# M5_CORE2_re.net
KiCad netlist of a schematic drawn in Altium Designer
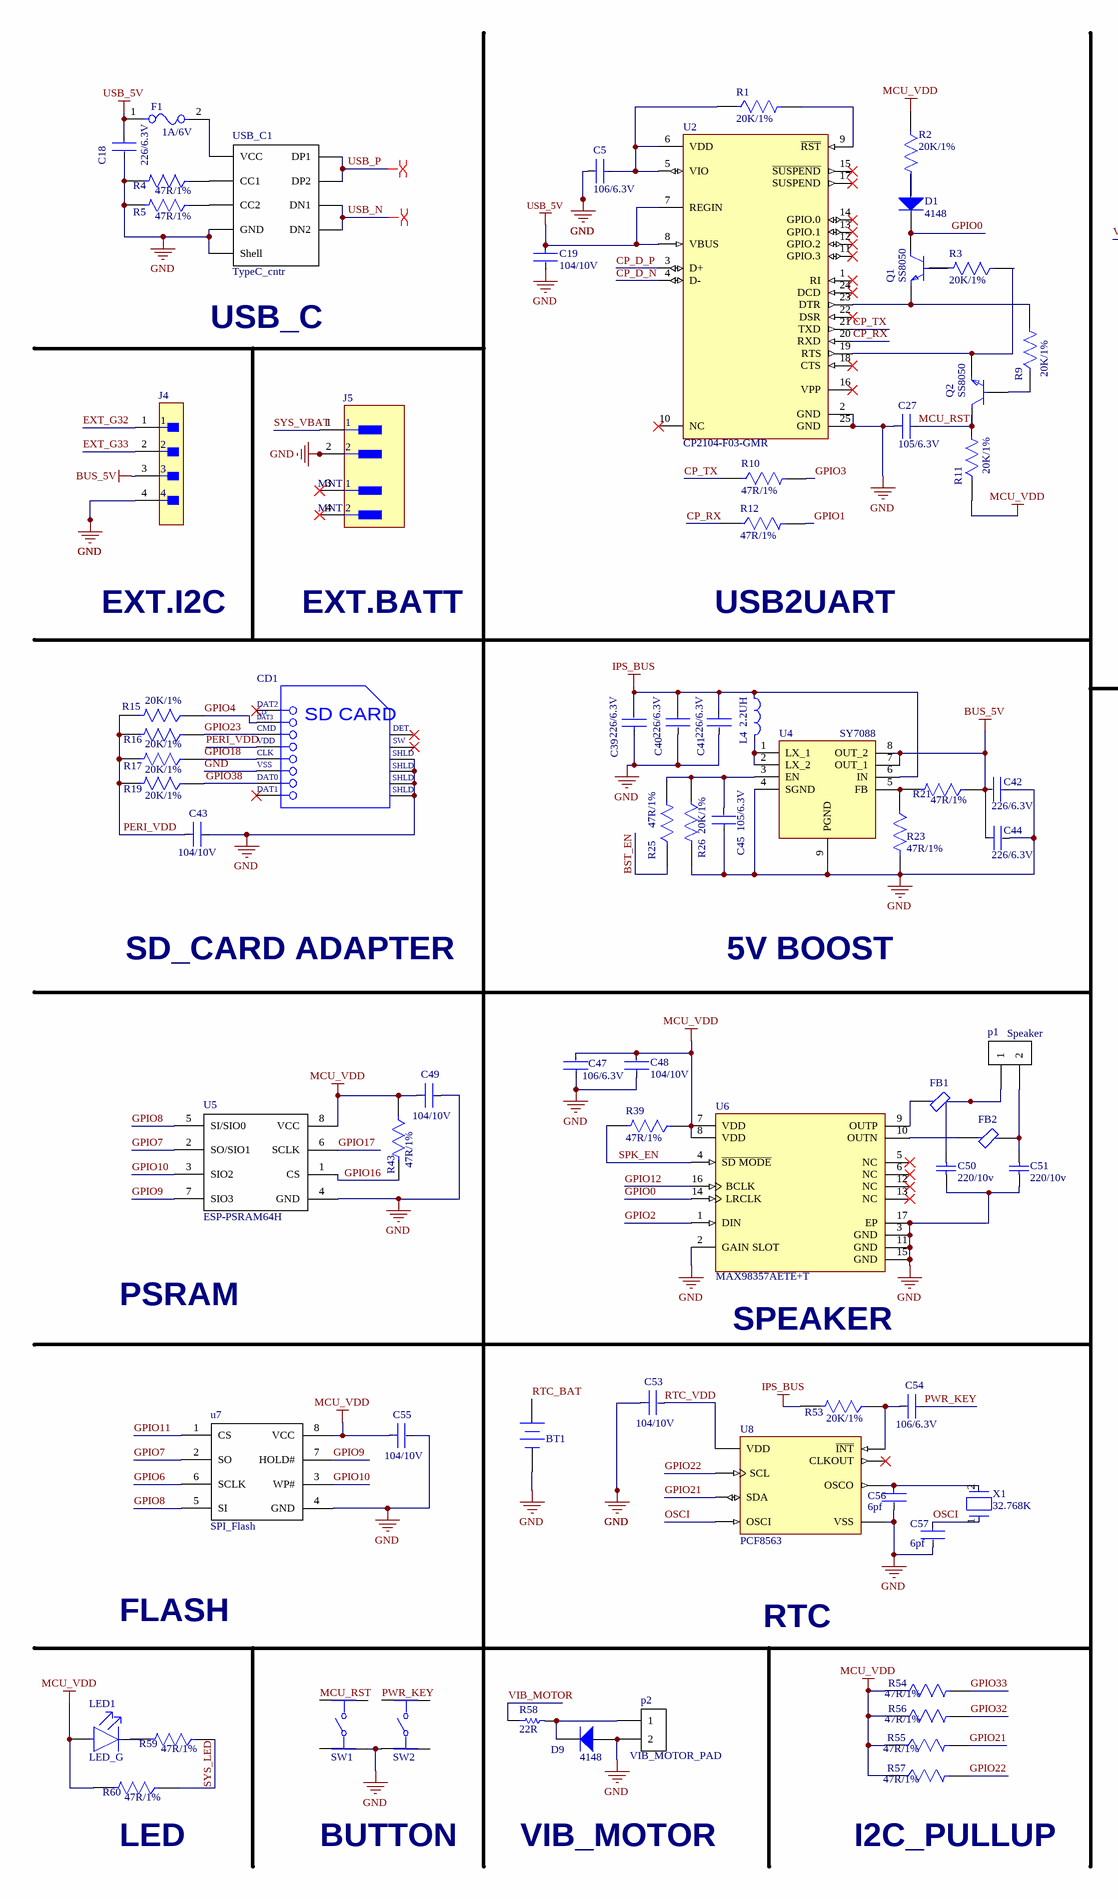
[diagram p0: M5_CORE2_re.SchDoc, left]
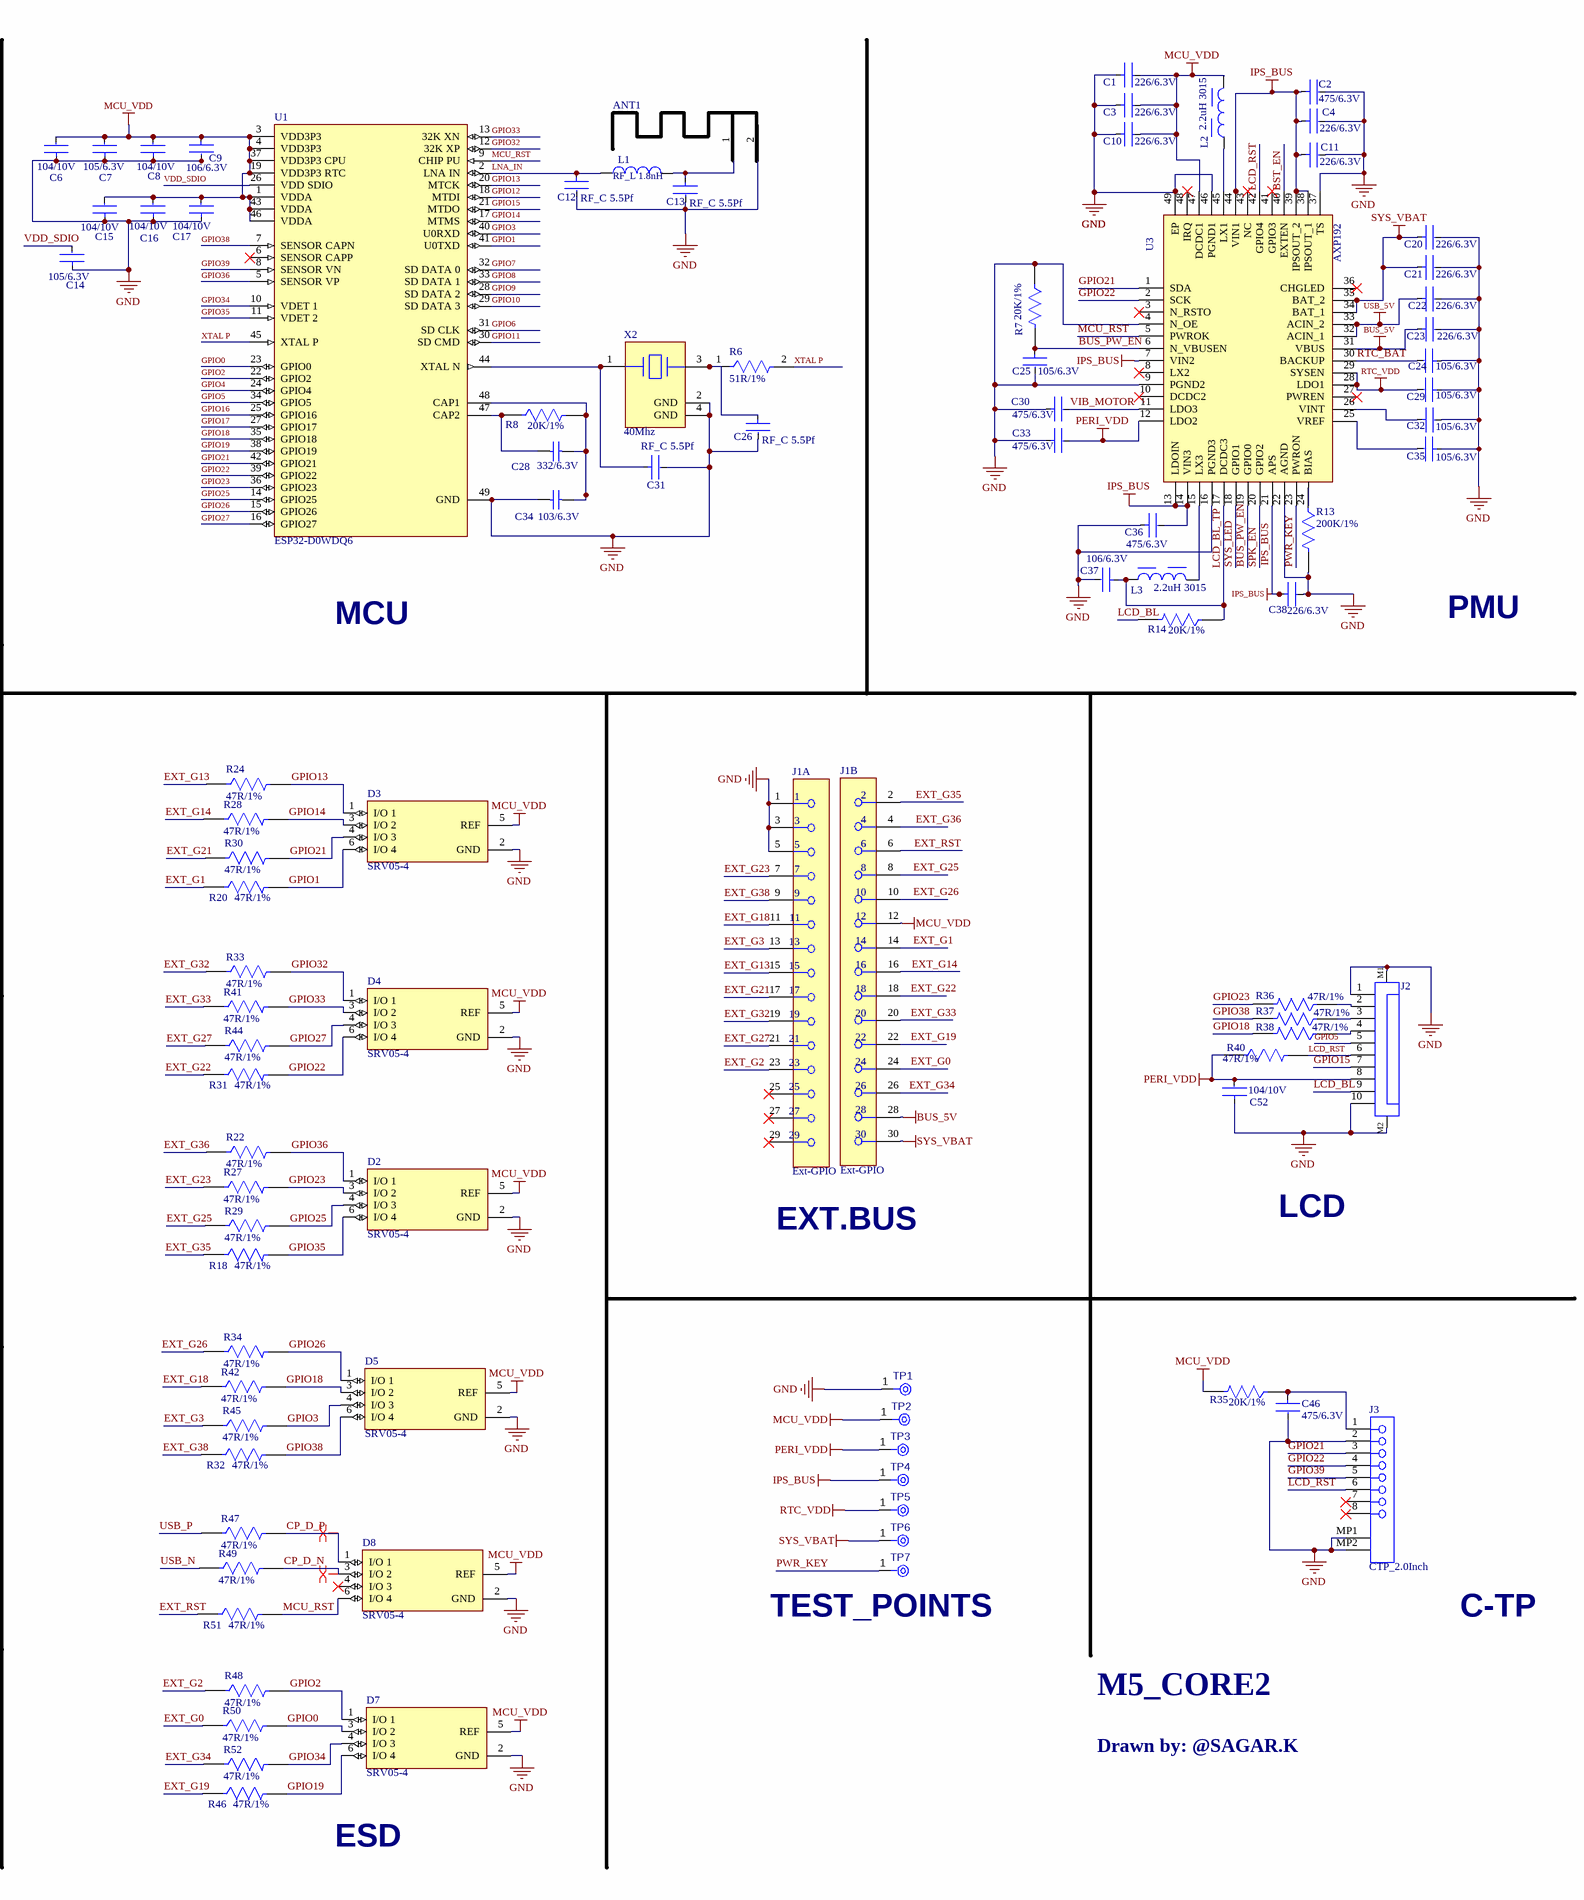
[diagram p1: M5_CORE2_re.SchDoc, right]

(export (version "E")
  (design (tool "Eeschema 10.0.6"))
  (components
    (comp (ref "ANT1")
      (value "2.4GHz_PCB-Antenna")
      (footprint "2.4GHZ_PCB-Antenna")
      (description "Generic symbol for PCB Antenna,")
      (libsource (lib "myLibs") (part "2.4GHz_PCB-Antenna"))
    )
    (comp (ref "BT1")
      (value "MS621FE-FL11E")
      (footprint "SEIK-MS621FE-FL11E-2_V")
      (description "MS Lihium Rechargeable Battery, 3 V, -20 to 60 degC, Tray")
      (fields (field (name "MANUFACTURER") "SeikoInstruments"))
      (libsource (lib "Altium Content Vault") (part "BATTERY_SINGLE-2"))
    )
    (comp (ref "C1")
      (value "226/6.3V")
      (footprint "FP-CL05A226MQ5N6J8-IPC_C")
      (description "CAP CER 22UF 6.3V X5R 0402")
      (fields
        (field (name "MANUFACTURER PART NUMBER") "CL05A226MQ5N6J8")
        (field (name "MANUFACTURER") "Samsung")
      )
      (libsource (lib "myLibs") (part "CMP-13271-000001-1"))
    )
    (comp (ref "C2")
      (value "475/6.3V")
      (footprint "FP-GRM155-0_1-IPC_B")
      (description "Chip Multilayer Ceramic Capacitors for General Purpose, 0402, 4.7uF, X5R, 15%, 20%, 6.3V")
      (fields (field (name "VOLTAGE") "6.3V") (field (name "TOLERANCE") "20%"))
      (libsource (lib "myLibs") (part "CMP-2008-04549-2"))
    )
    (comp (ref "C3")
      (value "226/6.3V")
      (footprint "FP-CL05A226MQ5N6J8-IPC_C")
      (description "CAP CER 22UF 6.3V X5R 0402")
      (fields
        (field (name "MANUFACTURER PART NUMBER") "CL05A226MQ5N6J8")
        (field (name "MANUFACTURER") "Samsung")
      )
      (libsource (lib "myLibs") (part "CMP-13271-000001-1"))
    )
    (comp (ref "C4")
      (value "226/6.3V")
      (footprint "FP-CL05A226MQ5N6J8-IPC_C")
      (description "CAP CER 22UF 6.3V X5R 0402")
      (fields
        (field (name "MANUFACTURER PART NUMBER") "CL05A226MQ5N6J8")
        (field (name "MANUFACTURER") "Samsung")
      )
      (libsource (lib "myLibs") (part "CMP-13271-000001-1"))
    )
    (comp (ref "C5")
      (value "106/6.3V")
      (footprint "FP-GRM155-0_1-IPC_B")
      (description "CAP CER 10UF 6.3V X5R 0603")
      (fields
        (field (name "MANUFACTURER PART NUMBER") "C0603C106M9PACTU")
        (field (name "MANUFACTURER") "KEMET")
      )
      (libsource (lib "myLibs") (part "CMP-2006-02285-3"))
    )
    (comp (ref "C6")
      (value "104/10V")
      (footprint "FP-C0402-BB-MFG")
      (description "CAP CER 0.1UF 10V X5R 0402")
      (fields (field (name "MANUFACTURER") "KEMET") (field (name "TOLERANCE") "0.1"))
      (libsource (lib "myLibs") (part "CMP-2008-02046-2"))
    )
    (comp (ref "C7")
      (value "105/6.3V")
      (footprint "FP-C0402C105K9PACTU-MFG")
      (description "CAP CER 1UF 6.3V X5R 0402")
      (fields (field (name "TOLERANCE") "10%") (field (name "VOLTAGE") "6.3V"))
      (libsource (lib "myLibs") (part "CMP-2008-02075-2"))
    )
    (comp (ref "C8")
      (value "104/10V")
      (footprint "FP-C0402-BB-MFG")
      (description "CAP CER 0.1UF 10V X5R 0402")
      (fields (field (name "MANUFACTURER") "KEMET") (field (name "TOLERANCE") "0.1"))
      (libsource (lib "myLibs") (part "CMP-2008-02046-2"))
    )
    (comp (ref "C9")
      (value "106/6.3V")
      (footprint "FP-GRM155-0_2-IPC_B")
      (description "CAP CER 10UF 6.3V X5R 0402")
      (fields (field (name "VOLTAGE") "6.3V") (field (name "TOLERANCE") "20%"))
      (libsource (lib "myLibs") (part "CMP-2000-05265-2"))
    )
    (comp (ref "C10")
      (value "226/6.3V")
      (footprint "FP-CL05A226MQ5N6J8-IPC_C")
      (description "CAP CER 22UF 6.3V X5R 0402")
      (fields
        (field (name "MANUFACTURER PART NUMBER") "CL05A226MQ5N6J8")
        (field (name "MANUFACTURER") "Samsung")
      )
      (libsource (lib "myLibs") (part "CMP-13271-000001-1"))
    )
    (comp (ref "C11")
      (value "226/6.3V")
      (footprint "FP-CL05A226MQ5N6J8-IPC_C")
      (description "CAP CER 22UF 6.3V X5R 0402")
      (fields
        (field (name "MANUFACTURER PART NUMBER") "CL05A226MQ5N6J8")
        (field (name "MANUFACTURER") "Samsung")
      )
      (libsource (lib "myLibs") (part "CMP-13271-000001-1"))
    )
    (comp (ref "C12")
      (value "RF_C 5.5Pf")
      (footprint "FP-GJM155-0_05-IPC_C")
      (description "Multi-Layer Ceramic Capacitor 5.5pF C0G  ±0.05pF 0402 Paper T/R")
      (fields
        (field (name "MANUFACTURER") "Murata")
        (field (name "MANUFACTURER PART NUMBER") "GJM1555C1H5R5WB01D")
      )
      (libsource (lib "myLibs") (part "CMP-06035-038280-1"))
    )
    (comp (ref "C13")
      (value "RF_C 5.5Pf")
      (footprint "FP-GJM155-0_05-IPC_C")
      (description "Multi-Layer Ceramic Capacitor 5.5pF C0G  ±0.05pF 0402 Paper T/R")
      (fields
        (field (name "MANUFACTURER") "Murata")
        (field (name "MANUFACTURER PART NUMBER") "GJM1555C1H5R5WB01D")
      )
      (libsource (lib "myLibs") (part "CMP-06035-038280-1"))
    )
    (comp (ref "C14")
      (value "105/6.3V")
      (footprint "FP-C0402C105K9PACTU-MFG")
      (description "CAP CER 1UF 6.3V X5R 0402")
      (fields (field (name "TOLERANCE") "10%") (field (name "VOLTAGE") "6.3V"))
      (libsource (lib "myLibs") (part "CMP-2008-02075-2"))
    )
    (comp (ref "C15")
      (value "104/10V")
      (footprint "FP-C0402-BB-MFG")
      (description "CAP CER 0.1UF 10V X5R 0402")
      (fields (field (name "MANUFACTURER") "KEMET") (field (name "TOLERANCE") "0.1"))
      (libsource (lib "myLibs") (part "CMP-2008-02046-2"))
    )
    (comp (ref "C16")
      (value "104/10V")
      (footprint "FP-C0402-BB-MFG")
      (description "CAP CER 0.1UF 10V X5R 0402")
      (fields (field (name "MANUFACTURER") "KEMET") (field (name "TOLERANCE") "0.1"))
      (libsource (lib "myLibs") (part "CMP-2008-02046-2"))
    )
    (comp (ref "C17")
      (value "104/10V")
      (footprint "FP-C0402-BB-MFG")
      (description "CAP CER 0.1UF 10V X5R 0402")
      (fields (field (name "MANUFACTURER") "KEMET") (field (name "TOLERANCE") "0.1"))
      (libsource (lib "myLibs") (part "CMP-2008-02046-2"))
    )
    (comp (ref "C18")
      (value "226/6.3V")
      (footprint "FP-CL05A226MQ5N6J8-IPC_C")
      (description "CAP CER 22UF 6.3V X5R 0402")
      (fields
        (field (name "MANUFACTURER PART NUMBER") "CL05A226MQ5N6J8")
        (field (name "MANUFACTURER") "Samsung")
      )
      (libsource (lib "myLibs") (part "CMP-13271-000001-1"))
    )
    (comp (ref "C19")
      (value "104/10V")
      (footprint "FP-C0402-BB-MFG")
      (description "CAP CER 0.1UF 10V X5R 0402")
      (fields (field (name "MANUFACTURER") "KEMET") (field (name "TOLERANCE") "0.1"))
      (libsource (lib "myLibs") (part "CMP-2008-02046-2"))
    )
    (comp (ref "C20")
      (value "226/6.3V")
      (footprint "FP-CL05A226MQ5N6J8-IPC_C")
      (description "CAP CER 22UF 6.3V X5R 0402")
      (fields
        (field (name "MANUFACTURER PART NUMBER") "CL05A226MQ5N6J8")
        (field (name "MANUFACTURER") "Samsung")
      )
      (libsource (lib "myLibs") (part "CMP-13271-000001-1"))
    )
    (comp (ref "C21")
      (value "226/6.3V")
      (footprint "FP-CL05A226MQ5N6J8-IPC_C")
      (description "CAP CER 22UF 6.3V X5R 0402")
      (fields
        (field (name "MANUFACTURER PART NUMBER") "CL05A226MQ5N6J8")
        (field (name "MANUFACTURER") "Samsung")
      )
      (libsource (lib "myLibs") (part "CMP-13271-000001-1"))
    )
    (comp (ref "C22")
      (value "226/6.3V")
      (footprint "FP-CL05A226MQ5N6J8-IPC_C")
      (description "CAP CER 22UF 6.3V X5R 0402")
      (fields
        (field (name "MANUFACTURER PART NUMBER") "CL05A226MQ5N6J8")
        (field (name "MANUFACTURER") "Samsung")
      )
      (libsource (lib "myLibs") (part "CMP-13271-000001-1"))
    )
    (comp (ref "C23")
      (value "226/6.3V")
      (footprint "FP-CL05A226MQ5N6J8-IPC_C")
      (description "CAP CER 22UF 6.3V X5R 0402")
      (fields
        (field (name "MANUFACTURER PART NUMBER") "CL05A226MQ5N6J8")
        (field (name "MANUFACTURER") "Samsung")
      )
      (libsource (lib "myLibs") (part "CMP-13271-000001-1"))
    )
    (comp (ref "C24")
      (value "105/6.3V")
      (footprint "FP-C0402C105K9PACTU-MFG")
      (description "CAP CER 1UF 6.3V X5R 0402")
      (fields (field (name "TOLERANCE") "10%") (field (name "VOLTAGE") "6.3V"))
      (libsource (lib "myLibs") (part "CMP-2008-02075-2"))
    )
    (comp (ref "C25")
      (value "105/6.3V")
      (footprint "FP-C0402C105K9PACTU-MFG")
      (description "CAP CER 1UF 6.3V X5R 0402")
      (fields (field (name "TOLERANCE") "10%") (field (name "VOLTAGE") "6.3V"))
      (libsource (lib "myLibs") (part "CMP-2008-02075-2"))
    )
    (comp (ref "C26")
      (value "RF_C 5.5Pf")
      (footprint "FP-GJM155-0_05-IPC_C")
      (description "Multi-Layer Ceramic Capacitor 5.5pF C0G  ±0.05pF 0402 Paper T/R")
      (fields
        (field (name "MANUFACTURER") "Murata")
        (field (name "MANUFACTURER PART NUMBER") "GJM1555C1H5R5WB01D")
      )
      (libsource (lib "myLibs") (part "CMP-06035-038280-1"))
    )
    (comp (ref "C27")
      (value "105/6.3V")
      (footprint "FP-C0402C105K9PACTU-MFG")
      (description "CAP CER 1UF 6.3V X5R 0402")
      (fields (field (name "TOLERANCE") "10%") (field (name "VOLTAGE") "6.3V"))
      (libsource (lib "myLibs") (part "CMP-2008-02075-2"))
    )
    (comp (ref "C28")
      (value "332/6.3V")
      (footprint "CAPC1005X55X30LL05T10")
      (fields
        (field (name "PART NUMBER") "C0402C332K9RACTU")
        (field (name "MANUFACTURER") "KEMET")
        (field (name "MANUFACTURER PART NUMBER") "C0402C332K9RAC")
      )
      (libsource (lib "myLibs") (part "CMP-1034-01766-2"))
    )
    (comp (ref "C29")
      (value "105/6.3V")
      (footprint "FP-C0402C105K9PACTU-MFG")
      (description "CAP CER 1UF 6.3V X5R 0402")
      (fields (field (name "TOLERANCE") "10%") (field (name "VOLTAGE") "6.3V"))
      (libsource (lib "myLibs") (part "CMP-2008-02075-2"))
    )
    (comp (ref "C30")
      (value "475/6.3V")
      (footprint "FP-GRM155-0_1-IPC_B")
      (description "Chip Multilayer Ceramic Capacitors for General Purpose, 0402, 4.7uF, X5R, 15%, 20%, 6.3V")
      (fields (field (name "VOLTAGE") "6.3V") (field (name "TOLERANCE") "20%"))
      (libsource (lib "myLibs") (part "CMP-2008-04549-2"))
    )
    (comp (ref "C31")
      (value "RF_C 5.5Pf")
      (footprint "FP-GJM155-0_05-IPC_C")
      (description "Multi-Layer Ceramic Capacitor 5.5pF C0G  ±0.05pF 0402 Paper T/R")
      (fields
        (field (name "MANUFACTURER") "Murata")
        (field (name "MANUFACTURER PART NUMBER") "GJM1555C1H5R5WB01D")
      )
      (libsource (lib "myLibs") (part "CMP-06035-038280-1"))
    )
    (comp (ref "C32")
      (value "105/6.3V")
      (footprint "FP-C0402C105K9PACTU-MFG")
      (description "CAP CER 1UF 6.3V X5R 0402")
      (fields (field (name "TOLERANCE") "10%") (field (name "VOLTAGE") "6.3V"))
      (libsource (lib "myLibs") (part "CMP-2008-02075-2"))
    )
    (comp (ref "C33")
      (value "475/6.3V")
      (footprint "FP-GRM155-0_1-IPC_B")
      (description "Chip Multilayer Ceramic Capacitors for General Purpose, 0402, 4.7uF, X5R, 15%, 20%, 6.3V")
      (fields (field (name "VOLTAGE") "6.3V") (field (name "TOLERANCE") "20%"))
      (libsource (lib "myLibs") (part "CMP-2008-04549-2"))
    )
    (comp (ref "C34")
      (value "103/6.3V")
      (footprint "CAPC1005X55X30LL05T10")
      (fields
        (field (name "MANUFACTURER") "KEMET")
        (field (name "PART NUMBER") "C0402C103K9RACTU")
        (field (name "MANUFACTURER PART NUMBER") "C0402C103K9RAC")
      )
      (libsource (lib "myLibs") (part "CMP-1034-01868-2"))
    )
    (comp (ref "C35")
      (value "105/6.3V")
      (footprint "FP-C0402C105K9PACTU-MFG")
      (description "CAP CER 1UF 6.3V X5R 0402")
      (fields (field (name "TOLERANCE") "10%") (field (name "VOLTAGE") "6.3V"))
      (libsource (lib "myLibs") (part "CMP-2008-02075-2"))
    )
    (comp (ref "C36")
      (value "475/6.3V")
      (footprint "FP-GRM155-0_1-IPC_B")
      (description "Chip Multilayer Ceramic Capacitors for General Purpose, 0402, 4.7uF, X5R, 15%, 20%, 6.3V")
      (fields (field (name "VOLTAGE") "6.3V") (field (name "TOLERANCE") "20%"))
      (libsource (lib "myLibs") (part "CMP-2008-04549-2"))
    )
    (comp (ref "C37")
      (value "106/6.3V")
      (footprint "FP-GRM155-0_1-IPC_B")
      (description "CAP CER 10UF 6.3V X5R 0603")
      (fields
        (field (name "MANUFACTURER PART NUMBER") "C0603C106M9PACTU")
        (field (name "MANUFACTURER") "KEMET")
      )
      (libsource (lib "myLibs") (part "CMP-2006-02285-3"))
    )
    (comp (ref "C38")
      (value "226/6.3V")
      (footprint "FP-CL05A226MQ5N6J8-IPC_C")
      (description "CAP CER 22UF 6.3V X5R 0402")
      (fields
        (field (name "MANUFACTURER PART NUMBER") "CL05A226MQ5N6J8")
        (field (name "MANUFACTURER") "Samsung")
      )
      (libsource (lib "myLibs") (part "CMP-13271-000001-1"))
    )
    (comp (ref "C39")
      (value "226/6.3V")
      (footprint "FP-CL05A226MQ5N6J8-IPC_C")
      (description "CAP CER 22UF 6.3V X5R 0402")
      (fields
        (field (name "MANUFACTURER PART NUMBER") "CL05A226MQ5N6J8")
        (field (name "MANUFACTURER") "Samsung")
      )
      (libsource (lib "myLibs") (part "CMP-13271-000001-1"))
    )
    (comp (ref "C40")
      (value "226/6.3V")
      (footprint "FP-CL05A226MQ5N6J8-IPC_C")
      (description "CAP CER 22UF 6.3V X5R 0402")
      (fields
        (field (name "MANUFACTURER PART NUMBER") "CL05A226MQ5N6J8")
        (field (name "MANUFACTURER") "Samsung")
      )
      (libsource (lib "myLibs") (part "CMP-13271-000001-1"))
    )
    (comp (ref "C41")
      (value "226/6.3V")
      (footprint "FP-CL05A226MQ5N6J8-IPC_C")
      (description "CAP CER 22UF 6.3V X5R 0402")
      (fields
        (field (name "MANUFACTURER PART NUMBER") "CL05A226MQ5N6J8")
        (field (name "MANUFACTURER") "Samsung")
      )
      (libsource (lib "myLibs") (part "CMP-13271-000001-1"))
    )
    (comp (ref "C42")
      (value "226/6.3V")
      (footprint "FP-CL05A226MQ5N6J8-IPC_C")
      (description "CAP CER 22UF 6.3V X5R 0402")
      (fields
        (field (name "MANUFACTURER PART NUMBER") "CL05A226MQ5N6J8")
        (field (name "MANUFACTURER") "Samsung")
      )
      (libsource (lib "myLibs") (part "CMP-13271-000001-1"))
    )
    (comp (ref "C43")
      (value "104/10V")
      (footprint "FP-C0402-BB-MFG")
      (description "CAP CER 0.1UF 10V X5R 0402")
      (fields (field (name "MANUFACTURER") "KEMET") (field (name "TOLERANCE") "0.1"))
      (libsource (lib "myLibs") (part "CMP-2008-02046-2"))
    )
    (comp (ref "C44")
      (value "226/6.3V")
      (footprint "FP-CL05A226MQ5N6J8-IPC_C")
      (description "CAP CER 22UF 6.3V X5R 0402")
      (fields
        (field (name "MANUFACTURER PART NUMBER") "CL05A226MQ5N6J8")
        (field (name "MANUFACTURER") "Samsung")
      )
      (libsource (lib "myLibs") (part "CMP-13271-000001-1"))
    )
    (comp (ref "C45")
      (value "105/6.3V")
      (footprint "FP-C0402C105K9PACTU-MFG")
      (description "CAP CER 1UF 6.3V X5R 0402")
      (fields (field (name "TOLERANCE") "10%") (field (name "VOLTAGE") "6.3V"))
      (libsource (lib "myLibs") (part "CMP-2008-02075-2"))
    )
    (comp (ref "C46")
      (value "475/6.3V")
      (footprint "FP-GRM155-0_1-IPC_B")
      (description "Chip Multilayer Ceramic Capacitors for General Purpose, 0402, 4.7uF, X5R, 15%, 20%, 6.3V")
      (fields (field (name "VOLTAGE") "6.3V") (field (name "TOLERANCE") "20%"))
      (libsource (lib "myLibs") (part "CMP-2008-04549-2"))
    )
    (comp (ref "C47")
      (value "106/6.3V")
      (footprint "FP-GRM155-0_1-IPC_B")
      (description "CAP CER 10UF 6.3V X5R 0603")
      (fields
        (field (name "MANUFACTURER PART NUMBER") "C0603C106M9PACTU")
        (field (name "MANUFACTURER") "KEMET")
      )
      (libsource (lib "myLibs") (part "CMP-2006-02285-3"))
    )
    (comp (ref "C48")
      (value "104/10V")
      (footprint "FP-C0402-BB-MFG")
      (description "CAP CER 0.1UF 10V X5R 0402")
      (fields (field (name "MANUFACTURER") "KEMET") (field (name "TOLERANCE") "0.1"))
      (libsource (lib "myLibs") (part "CMP-2008-02046-2"))
    )
    (comp (ref "C49")
      (value "104/10V")
      (footprint "FP-C0402-BB-MFG")
      (description "CAP CER 0.1UF 10V X5R 0402")
      (fields (field (name "MANUFACTURER") "KEMET") (field (name "TOLERANCE") "0.1"))
      (libsource (lib "myLibs") (part "CMP-2008-02046-2"))
    )
    (comp (ref "C50")
      (value "220/10v")
      (footprint "CAPC1005X56X25LL10T15")
      (fields (field (name "PART NUMBER") "0402ZC221KAT2A") (field (name "MANUFACTURER") "Kyocera AVX"))
      (libsource (lib "myLibs") (part "CMP-2008-02969-1"))
    )
    (comp (ref "C51")
      (value "220/10v")
      (footprint "CAPC1005X56X25LL10T15")
      (fields (field (name "PART NUMBER") "0402ZC221KAT2A") (field (name "MANUFACTURER") "Kyocera AVX"))
      (libsource (lib "myLibs") (part "CMP-2008-02969-1"))
    )
    (comp (ref "C52")
      (value "104/10V")
      (footprint "FP-C0402-BB-MFG")
      (description "CAP CER 0.1UF 10V X5R 0402")
      (fields (field (name "MANUFACTURER") "KEMET") (field (name "TOLERANCE") "0.1"))
      (libsource (lib "myLibs") (part "CMP-2008-02046-2"))
    )
    (comp (ref "C53")
      (value "104/10V")
      (footprint "FP-C0402-BB-MFG")
      (description "CAP CER 0.1UF 10V X5R 0402")
      (fields (field (name "MANUFACTURER") "KEMET") (field (name "TOLERANCE") "0.1"))
      (libsource (lib "myLibs") (part "CMP-2008-02046-2"))
    )
    (comp (ref "C54")
      (value "106/6.3V")
      (footprint "FP-GRM155-0_1-IPC_B")
      (description "CAP CER 10UF 6.3V X5R 0603")
      (fields
        (field (name "MANUFACTURER PART NUMBER") "C0603C106M9PACTU")
        (field (name "MANUFACTURER") "KEMET")
      )
      (libsource (lib "myLibs") (part "CMP-2006-02285-3"))
    )
    (comp (ref "C55")
      (value "104/10V")
      (footprint "FP-C0402-BB-MFG")
      (description "CAP CER 0.1UF 10V X5R 0402")
      (fields (field (name "MANUFACTURER") "KEMET") (field (name "TOLERANCE") "0.1"))
      (libsource (lib "myLibs") (part "CMP-2008-02046-2"))
    )
    (comp (ref "C56")
      (value "6pf")
      (footprint "FP-CGA2B-IPC_A")
      (description "Cap Ceramic 6pF 50V C0G 0.5pF Pad SMD 0402 +125°C Automotive T/R")
      (fields
        (field (name "MANUFACTURER") "TDK")
        (field (name "MANUFACTURER PART NUMBER") "CGA2B2C0G1H060D050BA")
      )
      (libsource (lib "myLibs") (part "CMP-08246-001536-1"))
    )
    (comp (ref "C57")
      (value "6pf")
      (footprint "FP-CGA2B-IPC_A")
      (description "Cap Ceramic 6pF 50V C0G 0.5pF Pad SMD 0402 +125°C Automotive T/R")
      (fields
        (field (name "MANUFACTURER") "TDK")
        (field (name "MANUFACTURER PART NUMBER") "CGA2B2C0G1H060D050BA")
      )
      (libsource (lib "myLibs") (part "CMP-08246-001536-1"))
    )
    (comp (ref "CD1")
      (value "502774-0891")
      (footprint "MOLX-502774-0891_V")
      (description "Micro SD Memory Card Connector, 0.5 A, 10 V (DC), -25 to 85 degC, 8-Pin SMT, RoHS, Tape and Reel")
      (fields (field (name "MANUFACTURER") "Molex"))
      (libsource (lib "Altium Content Vault") (part "CN-SD-8-2SW-4S_B"))
    )
    (comp (ref "D1")
      (value "4148")
      (footprint "FP-SOD323-MFG")
      (description "Switching Diode, 2-Pin SOD-123, Pb-Free, Tape and Reel")
      (fields (field (name "PARTNUMBER") "MMSD4148T1G") (field (name "MANUFACTURER") "ON Semiconductor"))
      (libsource (lib "myLibs") (part "CMP-0895-00001-2"))
    )
    (comp (ref "D2")
      (value "SRV05-4")
      (footprint "FP-CDSOT23-SRV05-4-MFG")
      (description "TVS DIODE 5V 15V SOT23-6")
      (fields
        (field (name "MANUFACTURER PART NUMBER") "CDSOT23-SRV05-4")
        (field (name "OCTOPART") "https://octopart.com/cdsot23-srv05-4-bourns-1679449")
      )
      (libsource (lib "myLibs") (part "CMP-07401-000007-1"))
    )
    (comp (ref "D3")
      (value "SRV05-4")
      (footprint "FP-CDSOT23-SRV05-4-MFG")
      (description "TVS DIODE 5V 15V SOT23-6")
      (fields
        (field (name "MANUFACTURER PART NUMBER") "CDSOT23-SRV05-4")
        (field (name "OCTOPART") "https://octopart.com/cdsot23-srv05-4-bourns-1679449")
      )
      (libsource (lib "myLibs") (part "CMP-07401-000007-1"))
    )
    (comp (ref "D4")
      (value "SRV05-4")
      (footprint "FP-CDSOT23-SRV05-4-MFG")
      (description "TVS DIODE 5V 15V SOT23-6")
      (fields
        (field (name "MANUFACTURER PART NUMBER") "CDSOT23-SRV05-4")
        (field (name "OCTOPART") "https://octopart.com/cdsot23-srv05-4-bourns-1679449")
      )
      (libsource (lib "myLibs") (part "CMP-07401-000007-1"))
    )
    (comp (ref "D5")
      (value "SRV05-4")
      (footprint "FP-CDSOT23-SRV05-4-MFG")
      (description "TVS DIODE 5V 15V SOT23-6")
      (fields
        (field (name "MANUFACTURER PART NUMBER") "CDSOT23-SRV05-4")
        (field (name "OCTOPART") "https://octopart.com/cdsot23-srv05-4-bourns-1679449")
      )
      (libsource (lib "myLibs") (part "CMP-07401-000007-1"))
    )
    (comp (ref "D7")
      (value "SRV05-4")
      (footprint "FP-CDSOT23-SRV05-4-MFG")
      (description "TVS DIODE 5V 15V SOT23-6")
      (fields
        (field (name "MANUFACTURER PART NUMBER") "CDSOT23-SRV05-4")
        (field (name "OCTOPART") "https://octopart.com/cdsot23-srv05-4-bourns-1679449")
      )
      (libsource (lib "myLibs") (part "CMP-07401-000007-1"))
    )
    (comp (ref "D8")
      (value "SRV05-4")
      (footprint "FP-CDSOT23-SRV05-4-MFG")
      (description "TVS DIODE 5V 15V SOT23-6")
      (fields
        (field (name "MANUFACTURER PART NUMBER") "CDSOT23-SRV05-4")
        (field (name "OCTOPART") "https://octopart.com/cdsot23-srv05-4-bourns-1679449")
      )
      (libsource (lib "myLibs") (part "CMP-07401-000007-1"))
    )
    (comp (ref "D9")
      (value "4148")
      (footprint "FP-SOD323-MFG")
      (description "Switching Diode, 2-Pin SOD-123, Pb-Free, Tape and Reel")
      (fields (field (name "PARTNUMBER") "MMSD4148T1G") (field (name "MANUFACTURER") "ON Semiconductor"))
      (libsource (lib "myLibs") (part "CMP-0895-00001-2"))
    )
    (comp (ref "F1")
      (value "1A/6V")
      (footprint "FP-0805L-MFG")
      (description "PTC RESET FUSE 6V 500MA 0805")
      (fields
        (field (name "MANUFACTURER PART NUMBER") "0805L050WR")
        (field (name "MANUFACTURER") "Littelfuse")
      )
      (libsource (lib "myLibs") (part "CMP-08606-000023-1"))
    )
    (comp (ref "FB1")
      (value "BLM15AG601SN1D")
      (footprint "FP-BLM15-0_05-MFG")
      (description "Chip Ferrite Bead, 0402, 600Ω @ 100MHz, 0.52Ω, 25%, 300mA")
      (fields (field (name "TOLERANCE") "25%") (field (name "MANUFACTURER") "Murata"))
      (libsource (lib "myLibs") (part "CMP-0686-00187-4"))
    )
    (comp (ref "FB2")
      (value "BLM15AG601SN1D")
      (footprint "FP-BLM15-0_05-MFG")
      (description "Chip Ferrite Bead, 0402, 600Ω @ 100MHz, 0.52Ω, 25%, 300mA")
      (fields (field (name "TOLERANCE") "25%") (field (name "MANUFACTURER") "Murata"))
      (libsource (lib "myLibs") (part "CMP-0686-00187-4"))
    )
    (comp (ref "J1")
      (value "Ext-GPIO")
      (footprint "FP-6-534206-5-MFG")
      (description "CONN RCPT 30POS 0.1 GOLD PCB")
      (fields
        (field (name "MANUFACTURER PART NUMBER") "6-534206-5")
        (field (name "MANUFACTURER") "TE Connectivity")
      )
      (libsource (lib "myLibs") (part "CMP-03369-000056-1"))
    )
    (comp (ref "J2")
      (value "687110149022")
      (footprint "687110149022")
      (libsource (lib "Altium Content Vault") (part "FPC - 10P - 2MP"))
    )
    (comp (ref "J3")
      (value "CTP_2.0Inch")
      (footprint "MOLX-52745-0897")
      (fields (field (name "PARTNUMBER") "52745-0897") (field (name "MANUFACTURER") "Molex"))
      (libsource (lib "myLibs") (part "CMP-1241-00354-1"))
    )
    (comp (ref "J4")
      (value "S4B-ZR(LF)(SN)")
      (footprint "FP-S4B-ZR_LF_SN-MFG")
      (description "CONN HEADER R/A 4POS 1.5MM")
      (fields
        (field (name "OCTOPART") "https://octopart.com/s4b-zr%28lf%29%28sn%29-jst-248835")
        (field (name "MANUFACTURER") "JST")
      )
      (libsource (lib "myLibs") (part "CMP-17439-000004-1"))
    )
    (comp (ref "J5")
      (value "BM02B-SRSS-TBT(LF)(SN)")
      (footprint "FP-BM02B-SRSS-TBT_LF_SN-MFG")
      (description "CONN WIRE HDR 2POS 1MM STSMD")
      (fields (field (name "MANUFACTURER") "JST"))
      (libsource (lib "myLibs") (part "CMP-17439-000179-1"))
    )
    (comp (ref "L1")
      (value "RF_L 1.8nH")
      (footprint "WE-TCI_0402")
      (description "744901018 Fixed Ind 1.8NH 560MA 200MOHM Sm")
      (fields
        (field (name "MANUFACTURER") "Wurth Electronics")
        (field (name "MANUFACTURER PART NUMBER") "744901018")
      )
      (libsource (lib "myLibs") (part "CMP-03913-14415874-1"))
    )
    (comp (ref "L2")
      (value "2.2uH 3015")
      (footprint "WE-MAPI_3015")
      (fields
        (field (name "TOLERANCE") "20%")
        (field (name "MANUFACTURER") "Wurth Electronics")
        (field (name "MANUFACTURER PART NUMBER") "74438335022")
      )
      (libsource (lib "myLibs") (part "CMP-1393-00018-2"))
    )
    (comp (ref "L3")
      (value "2.2uH 3015")
      (footprint "WE-MAPI_3015")
      (fields
        (field (name "TOLERANCE") "20%")
        (field (name "MANUFACTURER") "Wurth Electronics")
        (field (name "MANUFACTURER PART NUMBER") "74438335022")
      )
      (libsource (lib "myLibs") (part "CMP-1393-00018-2"))
    )
    (comp (ref "L4")
      (value "2.2UH")
      (footprint "FP-LQM2HPN_G0-IPC_C")
      (description "Multilayer Type Inductor for Power Lines, 1008 (2520), 2.2μH, 20%, 0.1Ω, 1.3A")
      (fields (field (name "TOLERANCE") "20%") (field (name "MANUFACTURER") "Murata"))
      (libsource (lib "myLibs") (part "CMP-1662-00028-2"))
    )
    (comp (ref "LED1")
      (value "LED_G")
      (footprint "FP-SML-P1-MFG")
      (description "LED GREEN CLEAR 1006 SMD")
      (fields (field (name "MANUFACTURER PART NUMBER") "SML-P13PTT86R") (field (name "MANUFACTURER") "Rohm"))
      (libsource (lib "myLibs") (part "CMP-08952-000015-1"))
    )
    (comp (ref "p1")
      (value "Speaker")
      (footprint "2pin SMD pads")
      (libsource (lib "myLibs") (part "2Pin SMD pad"))
    )
    (comp (ref "p2")
      (value "VIB_MOTOR_PAD")
      (footprint "2pin SMD pads")
      (libsource (lib "myLibs") (part "2Pin SMD pad"))
    )
    (comp (ref "Q1")
      (value "SS8050")
      (footprint "FP-SS8050-G-MFG")
      (description "NPN TRANSISTOR 1.5A 40V SOT-23 R")
      (fields (field (name "MANUFACTURER") "Comchip") (field (name "MANUFACTURER PART NUMBER") "SS8050-G"))
      (libsource (lib "myLibs") (part "CMP-20235-000001-1"))
    )
    (comp (ref "Q2")
      (value "SS8050")
      (footprint "FP-SS8050-G-MFG")
      (description "NPN TRANSISTOR 1.5A 40V SOT-23 R")
      (fields (field (name "MANUFACTURER") "Comchip") (field (name "MANUFACTURER PART NUMBER") "SS8050-G"))
      (libsource (lib "myLibs") (part "CMP-20235-000001-1"))
    )
    (comp (ref "R1")
      (value "20K/1%")
      (footprint "FP-ERJ2RK-IPC_C")
      (description "RES SMD 20K OHM 1% 1/10W 0402")
      (fields (field (name "TOLERANCE") "1%") (field (name "MANUFACTURER") "Panasonic"))
      (libsource (lib "myLibs") (part "CMP-2002-00759-4"))
    )
    (comp (ref "R2")
      (value "20K/1%")
      (footprint "FP-ERJ2RK-IPC_C")
      (description "RES SMD 20K OHM 1% 1/10W 0402")
      (fields (field (name "TOLERANCE") "1%") (field (name "MANUFACTURER") "Panasonic"))
      (libsource (lib "myLibs") (part "CMP-2002-00759-4"))
    )
    (comp (ref "R3")
      (value "20K/1%")
      (footprint "FP-ERJ2RK-IPC_C")
      (description "RES SMD 20K OHM 1% 1/10W 0402")
      (fields (field (name "TOLERANCE") "1%") (field (name "MANUFACTURER") "Panasonic"))
      (libsource (lib "myLibs") (part "CMP-2002-00759-4"))
    )
    (comp (ref "R4")
      (value "47R/1%")
      (footprint "FP-ERJ2RK-IPC_C")
      (description "RES SMD 47 OHM 1% 1/10W 0402")
      (fields (field (name "TOLERANCE") "1%") (field (name "MANUFACTURER") "Vishay Dale"))
      (libsource (lib "myLibs") (part "CMP-1011-00360-3"))
    )
    (comp (ref "R5")
      (value "47R/1%")
      (footprint "FP-ERJ2RK-IPC_C")
      (description "RES SMD 47 OHM 1% 1/10W 0402")
      (fields (field (name "TOLERANCE") "1%") (field (name "MANUFACTURER") "Vishay Dale"))
      (libsource (lib "myLibs") (part "CMP-1011-00360-3"))
    )
    (comp (ref "R6")
      (value "51R/1%")
      (footprint "FP-CR0402-IPC_A")
      (description "Thick Film Chip Resistors 0402 51Ω 0.0625W 1% 100ppm/°C")
      (fields (field (name "TOLERANCE") "1%") (field (name "MANUFACTURER") "Bourns"))
      (libsource (lib "myLibs") (part "CMP-2002-05265-2"))
    )
    (comp (ref "R7")
      (value "20K/1%")
      (footprint "FP-ERJ2RK-IPC_C")
      (description "RES SMD 20K OHM 1% 1/10W 0402")
      (fields (field (name "TOLERANCE") "1%") (field (name "MANUFACTURER") "Panasonic"))
      (libsource (lib "myLibs") (part "CMP-2002-00759-4"))
    )
    (comp (ref "R8")
      (value "20K/1%")
      (footprint "FP-ERJ2RK-IPC_C")
      (description "RES SMD 20K OHM 1% 1/10W 0402")
      (fields (field (name "TOLERANCE") "1%") (field (name "MANUFACTURER") "Panasonic"))
      (libsource (lib "myLibs") (part "CMP-2002-00759-4"))
    )
    (comp (ref "R9")
      (value "20K/1%")
      (footprint "FP-ERJ2RK-IPC_C")
      (description "RES SMD 20K OHM 1% 1/10W 0402")
      (fields (field (name "TOLERANCE") "1%") (field (name "MANUFACTURER") "Panasonic"))
      (libsource (lib "myLibs") (part "CMP-2002-00759-4"))
    )
    (comp (ref "R10")
      (value "47R/1%")
      (footprint "FP-ERJ2RK-IPC_C")
      (description "RES SMD 47 OHM 1% 1/10W 0402")
      (fields (field (name "TOLERANCE") "1%") (field (name "MANUFACTURER") "Vishay Dale"))
      (libsource (lib "myLibs") (part "CMP-1011-00360-3"))
    )
    (comp (ref "R11")
      (value "20K/1%")
      (footprint "FP-ERJ2RK-IPC_C")
      (description "RES SMD 20K OHM 1% 1/10W 0402")
      (fields (field (name "TOLERANCE") "1%") (field (name "MANUFACTURER") "Panasonic"))
      (libsource (lib "myLibs") (part "CMP-2002-00759-4"))
    )
    (comp (ref "R12")
      (value "47R/1%")
      (footprint "FP-ERJ2RK-IPC_C")
      (description "RES SMD 47 OHM 1% 1/10W 0402")
      (fields (field (name "TOLERANCE") "1%") (field (name "MANUFACTURER") "Vishay Dale"))
      (libsource (lib "myLibs") (part "CMP-1011-00360-3"))
    )
    (comp (ref "R13")
      (value "200K/1%")
      (footprint "FP-RMCF0402-IPC_C")
      (description "200kΩ ±1% 0.063W 0402 Thick Film Chip Resistor AEC-Q200 compliant")
      (fields (field (name "TOLERANCE") "1%") (field (name "MANUFACTURER") "Stackpole Electronics"))
      (libsource (lib "myLibs") (part "CMP-26527-000100-1"))
    )
    (comp (ref "R14")
      (value "20K/1%")
      (footprint "FP-ERJ2RK-IPC_C")
      (description "RES SMD 20K OHM 1% 1/10W 0402")
      (fields (field (name "TOLERANCE") "1%") (field (name "MANUFACTURER") "Panasonic"))
      (libsource (lib "myLibs") (part "CMP-2002-00759-4"))
    )
    (comp (ref "R15")
      (value "20K/1%")
      (footprint "FP-ERJ2RK-IPC_C")
      (description "RES SMD 20K OHM 1% 1/10W 0402")
      (fields (field (name "TOLERANCE") "1%") (field (name "MANUFACTURER") "Panasonic"))
      (libsource (lib "myLibs") (part "CMP-2002-00759-4"))
    )
    (comp (ref "R16")
      (value "20K/1%")
      (footprint "FP-ERJ2RK-IPC_C")
      (description "RES SMD 20K OHM 1% 1/10W 0402")
      (fields (field (name "TOLERANCE") "1%") (field (name "MANUFACTURER") "Panasonic"))
      (libsource (lib "myLibs") (part "CMP-2002-00759-4"))
    )
    (comp (ref "R17")
      (value "20K/1%")
      (footprint "FP-ERJ2RK-IPC_C")
      (description "RES SMD 20K OHM 1% 1/10W 0402")
      (fields (field (name "TOLERANCE") "1%") (field (name "MANUFACTURER") "Panasonic"))
      (libsource (lib "myLibs") (part "CMP-2002-00759-4"))
    )
    (comp (ref "R18")
      (value "47R/1%")
      (footprint "FP-ERJ2RK-IPC_C")
      (description "RES SMD 47 OHM 1% 1/10W 0402")
      (fields (field (name "TOLERANCE") "1%") (field (name "MANUFACTURER") "Vishay Dale"))
      (libsource (lib "myLibs") (part "CMP-1011-00360-3"))
    )
    (comp (ref "R19")
      (value "20K/1%")
      (footprint "FP-ERJ2RK-IPC_C")
      (description "RES SMD 20K OHM 1% 1/10W 0402")
      (fields (field (name "TOLERANCE") "1%") (field (name "MANUFACTURER") "Panasonic"))
      (libsource (lib "myLibs") (part "CMP-2002-00759-4"))
    )
    (comp (ref "R20")
      (value "47R/1%")
      (footprint "FP-ERJ2RK-IPC_C")
      (description "RES SMD 47 OHM 1% 1/10W 0402")
      (fields (field (name "TOLERANCE") "1%") (field (name "MANUFACTURER") "Vishay Dale"))
      (libsource (lib "myLibs") (part "CMP-1011-00360-3"))
    )
    (comp (ref "R21")
      (value "47R/1%")
      (footprint "FP-ERJ2RK-IPC_C")
      (description "RES SMD 47 OHM 1% 1/10W 0402")
      (fields (field (name "TOLERANCE") "1%") (field (name "MANUFACTURER") "Vishay Dale"))
      (libsource (lib "myLibs") (part "CMP-1011-00360-3"))
    )
    (comp (ref "R22")
      (value "47R/1%")
      (footprint "FP-ERJ2RK-IPC_C")
      (description "RES SMD 47 OHM 1% 1/10W 0402")
      (fields (field (name "TOLERANCE") "1%") (field (name "MANUFACTURER") "Vishay Dale"))
      (libsource (lib "myLibs") (part "CMP-1011-00360-3"))
    )
    (comp (ref "R23")
      (value "47R/1%")
      (footprint "FP-ERJ2RK-IPC_C")
      (description "RES SMD 47 OHM 1% 1/10W 0402")
      (fields (field (name "TOLERANCE") "1%") (field (name "MANUFACTURER") "Vishay Dale"))
      (libsource (lib "myLibs") (part "CMP-1011-00360-3"))
    )
    (comp (ref "R24")
      (value "47R/1%")
      (footprint "FP-ERJ2RK-IPC_C")
      (description "RES SMD 47 OHM 1% 1/10W 0402")
      (fields (field (name "TOLERANCE") "1%") (field (name "MANUFACTURER") "Vishay Dale"))
      (libsource (lib "myLibs") (part "CMP-1011-00360-3"))
    )
    (comp (ref "R25")
      (value "47R/1%")
      (footprint "FP-ERJ2RK-IPC_C")
      (description "RES SMD 47 OHM 1% 1/10W 0402")
      (fields (field (name "TOLERANCE") "1%") (field (name "MANUFACTURER") "Vishay Dale"))
      (libsource (lib "myLibs") (part "CMP-1011-00360-3"))
    )
    (comp (ref "R26")
      (value "20K/1%")
      (footprint "FP-ERJ2RK-IPC_C")
      (description "RES SMD 20K OHM 1% 1/10W 0402")
      (fields (field (name "TOLERANCE") "1%") (field (name "MANUFACTURER") "Panasonic"))
      (libsource (lib "myLibs") (part "CMP-2002-00759-4"))
    )
    (comp (ref "R27")
      (value "47R/1%")
      (footprint "FP-ERJ2RK-IPC_C")
      (description "RES SMD 47 OHM 1% 1/10W 0402")
      (fields (field (name "TOLERANCE") "1%") (field (name "MANUFACTURER") "Vishay Dale"))
      (libsource (lib "myLibs") (part "CMP-1011-00360-3"))
    )
    (comp (ref "R28")
      (value "47R/1%")
      (footprint "FP-ERJ2RK-IPC_C")
      (description "RES SMD 47 OHM 1% 1/10W 0402")
      (fields (field (name "TOLERANCE") "1%") (field (name "MANUFACTURER") "Vishay Dale"))
      (libsource (lib "myLibs") (part "CMP-1011-00360-3"))
    )
    (comp (ref "R29")
      (value "47R/1%")
      (footprint "FP-ERJ2RK-IPC_C")
      (description "RES SMD 47 OHM 1% 1/10W 0402")
      (fields (field (name "TOLERANCE") "1%") (field (name "MANUFACTURER") "Vishay Dale"))
      (libsource (lib "myLibs") (part "CMP-1011-00360-3"))
    )
    (comp (ref "R30")
      (value "47R/1%")
      (footprint "FP-ERJ2RK-IPC_C")
      (description "RES SMD 47 OHM 1% 1/10W 0402")
      (fields (field (name "TOLERANCE") "1%") (field (name "MANUFACTURER") "Vishay Dale"))
      (libsource (lib "myLibs") (part "CMP-1011-00360-3"))
    )
    (comp (ref "R31")
      (value "47R/1%")
      (footprint "FP-ERJ2RK-IPC_C")
      (description "RES SMD 47 OHM 1% 1/10W 0402")
      (fields (field (name "TOLERANCE") "1%") (field (name "MANUFACTURER") "Vishay Dale"))
      (libsource (lib "myLibs") (part "CMP-1011-00360-3"))
    )
    (comp (ref "R32")
      (value "47R/1%")
      (footprint "FP-ERJ2RK-IPC_C")
      (description "RES SMD 47 OHM 1% 1/10W 0402")
      (fields (field (name "TOLERANCE") "1%") (field (name "MANUFACTURER") "Vishay Dale"))
      (libsource (lib "myLibs") (part "CMP-1011-00360-3"))
    )
    (comp (ref "R33")
      (value "47R/1%")
      (footprint "FP-ERJ2RK-IPC_C")
      (description "RES SMD 47 OHM 1% 1/10W 0402")
      (fields (field (name "TOLERANCE") "1%") (field (name "MANUFACTURER") "Vishay Dale"))
      (libsource (lib "myLibs") (part "CMP-1011-00360-3"))
    )
    (comp (ref "R34")
      (value "47R/1%")
      (footprint "FP-ERJ2RK-IPC_C")
      (description "RES SMD 47 OHM 1% 1/10W 0402")
      (fields (field (name "TOLERANCE") "1%") (field (name "MANUFACTURER") "Vishay Dale"))
      (libsource (lib "myLibs") (part "CMP-1011-00360-3"))
    )
    (comp (ref "R35")
      (value "20K/1%")
      (footprint "FP-ERJ2RK-IPC_C")
      (description "RES SMD 20K OHM 1% 1/10W 0402")
      (fields (field (name "TOLERANCE") "1%") (field (name "MANUFACTURER") "Panasonic"))
      (libsource (lib "myLibs") (part "CMP-2002-00759-4"))
    )
    (comp (ref "R36")
      (value "47R/1%")
      (footprint "FP-ERJ2RK-IPC_C")
      (description "RES SMD 47 OHM 1% 1/10W 0402")
      (fields (field (name "TOLERANCE") "1%") (field (name "MANUFACTURER") "Vishay Dale"))
      (libsource (lib "myLibs") (part "CMP-1011-00360-3"))
    )
    (comp (ref "R37")
      (value "47R/1%")
      (footprint "FP-ERJ2RK-IPC_C")
      (description "RES SMD 47 OHM 1% 1/10W 0402")
      (fields (field (name "TOLERANCE") "1%") (field (name "MANUFACTURER") "Vishay Dale"))
      (libsource (lib "myLibs") (part "CMP-1011-00360-3"))
    )
    (comp (ref "R38")
      (value "47R/1%")
      (footprint "FP-ERJ2RK-IPC_C")
      (description "RES SMD 47 OHM 1% 1/10W 0402")
      (fields (field (name "TOLERANCE") "1%") (field (name "MANUFACTURER") "Vishay Dale"))
      (libsource (lib "myLibs") (part "CMP-1011-00360-3"))
    )
    (comp (ref "R39")
      (value "47R/1%")
      (footprint "FP-ERJ2RK-IPC_C")
      (description "RES SMD 47 OHM 1% 1/10W 0402")
      (fields (field (name "TOLERANCE") "1%") (field (name "MANUFACTURER") "Vishay Dale"))
      (libsource (lib "myLibs") (part "CMP-1011-00360-3"))
    )
    (comp (ref "R40")
      (value "47R/1%")
      (footprint "FP-ERJ2RK-IPC_C")
      (description "RES SMD 47 OHM 1% 1/10W 0402")
      (fields (field (name "TOLERANCE") "1%") (field (name "MANUFACTURER") "Vishay Dale"))
      (libsource (lib "myLibs") (part "CMP-1011-00360-3"))
    )
    (comp (ref "R41")
      (value "47R/1%")
      (footprint "FP-ERJ2RK-IPC_C")
      (description "RES SMD 47 OHM 1% 1/10W 0402")
      (fields (field (name "TOLERANCE") "1%") (field (name "MANUFACTURER") "Vishay Dale"))
      (libsource (lib "myLibs") (part "CMP-1011-00360-3"))
    )
    (comp (ref "R42")
      (value "47R/1%")
      (footprint "FP-ERJ2RK-IPC_C")
      (description "RES SMD 47 OHM 1% 1/10W 0402")
      (fields (field (name "TOLERANCE") "1%") (field (name "MANUFACTURER") "Vishay Dale"))
      (libsource (lib "myLibs") (part "CMP-1011-00360-3"))
    )
    (comp (ref "R43")
      (value "47R/1%")
      (footprint "FP-ERJ2RK-IPC_C")
      (description "RES SMD 47 OHM 1% 1/10W 0402")
      (fields (field (name "TOLERANCE") "1%") (field (name "MANUFACTURER") "Vishay Dale"))
      (libsource (lib "myLibs") (part "CMP-1011-00360-3"))
    )
    (comp (ref "R44")
      (value "47R/1%")
      (footprint "FP-ERJ2RK-IPC_C")
      (description "RES SMD 47 OHM 1% 1/10W 0402")
      (fields (field (name "TOLERANCE") "1%") (field (name "MANUFACTURER") "Vishay Dale"))
      (libsource (lib "myLibs") (part "CMP-1011-00360-3"))
    )
    (comp (ref "R45")
      (value "47R/1%")
      (footprint "FP-ERJ2RK-IPC_C")
      (description "RES SMD 47 OHM 1% 1/10W 0402")
      (fields (field (name "TOLERANCE") "1%") (field (name "MANUFACTURER") "Vishay Dale"))
      (libsource (lib "myLibs") (part "CMP-1011-00360-3"))
    )
    (comp (ref "R46")
      (value "47R/1%")
      (footprint "FP-ERJ2RK-IPC_C")
      (description "RES SMD 47 OHM 1% 1/10W 0402")
      (fields (field (name "TOLERANCE") "1%") (field (name "MANUFACTURER") "Vishay Dale"))
      (libsource (lib "myLibs") (part "CMP-1011-00360-3"))
    )
    (comp (ref "R47")
      (value "47R/1%")
      (footprint "FP-ERJ2RK-IPC_C")
      (description "RES SMD 47 OHM 1% 1/10W 0402")
      (fields (field (name "TOLERANCE") "1%") (field (name "MANUFACTURER") "Vishay Dale"))
      (libsource (lib "myLibs") (part "CMP-1011-00360-3"))
    )
    (comp (ref "R48")
      (value "47R/1%")
      (footprint "FP-ERJ2RK-IPC_C")
      (description "RES SMD 47 OHM 1% 1/10W 0402")
      (fields (field (name "TOLERANCE") "1%") (field (name "MANUFACTURER") "Vishay Dale"))
      (libsource (lib "myLibs") (part "CMP-1011-00360-3"))
    )
    (comp (ref "R49")
      (value "47R/1%")
      (footprint "FP-ERJ2RK-IPC_C")
      (description "RES SMD 47 OHM 1% 1/10W 0402")
      (fields (field (name "TOLERANCE") "1%") (field (name "MANUFACTURER") "Vishay Dale"))
      (libsource (lib "myLibs") (part "CMP-1011-00360-3"))
    )
    (comp (ref "R50")
      (value "47R/1%")
      (footprint "FP-ERJ2RK-IPC_C")
      (description "RES SMD 47 OHM 1% 1/10W 0402")
      (fields (field (name "TOLERANCE") "1%") (field (name "MANUFACTURER") "Vishay Dale"))
      (libsource (lib "myLibs") (part "CMP-1011-00360-3"))
    )
    (comp (ref "R51")
      (value "47R/1%")
      (footprint "FP-ERJ2RK-IPC_C")
      (description "RES SMD 47 OHM 1% 1/10W 0402")
      (fields (field (name "TOLERANCE") "1%") (field (name "MANUFACTURER") "Vishay Dale"))
      (libsource (lib "myLibs") (part "CMP-1011-00360-3"))
    )
    (comp (ref "R52")
      (value "47R/1%")
      (footprint "FP-ERJ2RK-IPC_C")
      (description "RES SMD 47 OHM 1% 1/10W 0402")
      (fields (field (name "TOLERANCE") "1%") (field (name "MANUFACTURER") "Vishay Dale"))
      (libsource (lib "myLibs") (part "CMP-1011-00360-3"))
    )
    (comp (ref "R53")
      (value "20K/1%")
      (footprint "FP-ERJ2RK-IPC_C")
      (description "RES SMD 20K OHM 1% 1/10W 0402")
      (fields (field (name "TOLERANCE") "1%") (field (name "MANUFACTURER") "Panasonic"))
      (libsource (lib "myLibs") (part "CMP-2002-00759-4"))
    )
    (comp (ref "R54")
      (value "47R/1%")
      (footprint "FP-ERJ2RK-IPC_C")
      (description "RES SMD 47 OHM 1% 1/10W 0402")
      (fields (field (name "TOLERANCE") "1%") (field (name "MANUFACTURER") "Vishay Dale"))
      (libsource (lib "myLibs") (part "CMP-1011-00360-3"))
    )
    (comp (ref "R55")
      (value "47R/1%")
      (footprint "FP-ERJ2RK-IPC_C")
      (description "RES SMD 47 OHM 1% 1/10W 0402")
      (fields (field (name "TOLERANCE") "1%") (field (name "MANUFACTURER") "Vishay Dale"))
      (libsource (lib "myLibs") (part "CMP-1011-00360-3"))
    )
    (comp (ref "R56")
      (value "47R/1%")
      (footprint "FP-ERJ2RK-IPC_C")
      (description "RES SMD 47 OHM 1% 1/10W 0402")
      (fields (field (name "TOLERANCE") "1%") (field (name "MANUFACTURER") "Vishay Dale"))
      (libsource (lib "myLibs") (part "CMP-1011-00360-3"))
    )
    (comp (ref "R57")
      (value "47R/1%")
      (footprint "FP-ERJ2RK-IPC_C")
      (description "RES SMD 47 OHM 1% 1/10W 0402")
      (fields (field (name "TOLERANCE") "1%") (field (name "MANUFACTURER") "Vishay Dale"))
      (libsource (lib "myLibs") (part "CMP-1011-00360-3"))
    )
    (comp (ref "R58")
      (value "22R")
      (footprint "RESC1005X40X25LL05T10")
      (fields (field (name "MANUFACTURER") "Yageo") (field (name "PART NUMBER") "RC0402FR-0722RL"))
      (libsource (lib "myLibs") (part "CMP-2002-07520-1"))
    )
    (comp (ref "R59")
      (value "47R/1%")
      (footprint "FP-ERJ2RK-IPC_C")
      (description "RES SMD 47 OHM 1% 1/10W 0402")
      (fields (field (name "TOLERANCE") "1%") (field (name "MANUFACTURER") "Vishay Dale"))
      (libsource (lib "myLibs") (part "CMP-1011-00360-3"))
    )
    (comp (ref "R60")
      (value "47R/1%")
      (footprint "FP-ERJ2RK-IPC_C")
      (description "RES SMD 47 OHM 1% 1/10W 0402")
      (fields (field (name "TOLERANCE") "1%") (field (name "MANUFACTURER") "Vishay Dale"))
      (libsource (lib "myLibs") (part "CMP-1011-00360-3"))
    )
    (comp (ref "SW1")
      (value "EVQ-PUC02K")
      (footprint "FP-EVQ-PUC02K-MFG")
      (description "SWITCH TACTILE SPST-NO 0.05A 12V")
      (fields (field (name "MANUFACTURER") "Panasonic"))
      (libsource (lib "myLibs") (part "CMP-05618-000046-1"))
    )
    (comp (ref "SW2")
      (value "EVQ-PUC02K")
      (footprint "FP-EVQ-PUC02K-MFG")
      (description "SWITCH TACTILE SPST-NO 0.05A 12V")
      (fields (field (name "MANUFACTURER") "Panasonic"))
      (libsource (lib "myLibs") (part "CMP-05618-000046-1"))
    )
    (comp (ref "TP1")
      (value "TPAD6R")
      (footprint "TP06R")
      (description "0.6mm round")
      (libsource (lib "myLibs") (part "CMP-00028-00002-2"))
    )
    (comp (ref "TP2")
      (value "TPAD6R")
      (footprint "TP06R")
      (description "0.6mm round")
      (libsource (lib "myLibs") (part "CMP-00028-00002-2"))
    )
    (comp (ref "TP3")
      (value "TPAD6R")
      (footprint "TP06R")
      (description "0.6mm round")
      (libsource (lib "myLibs") (part "CMP-00028-00002-2"))
    )
    (comp (ref "TP4")
      (value "TPAD6R")
      (footprint "TP06R")
      (description "0.6mm round")
      (libsource (lib "myLibs") (part "CMP-00028-00002-2"))
    )
    (comp (ref "TP5")
      (value "TPAD6R")
      (footprint "TP06R")
      (description "0.6mm round")
      (libsource (lib "myLibs") (part "CMP-00028-00002-2"))
    )
    (comp (ref "TP6")
      (value "TPAD6R")
      (footprint "TP06R")
      (description "0.6mm round")
      (libsource (lib "myLibs") (part "CMP-00028-00002-2"))
    )
    (comp (ref "TP7")
      (value "TPAD6R")
      (footprint "TP06R")
      (description "0.6mm round")
      (libsource (lib "myLibs") (part "CMP-00028-00002-2"))
    )
    (comp (ref "U1")
      (value "ESP32-D0WDQ6")
      (footprint "FP-ESP32-D0WDQ6-IPC_C")
      (description "IC RF TXRX+MCU BLUETOOTH 48VFQFN")
      (fields (field (name "MANUFACTURER") "Espressif Systems"))
      (libsource (lib "myLibs") (part "CMP-194065-000007-1"))
    )
    (comp (ref "U2")
      (value "CP2104-F03-GMR")
      (footprint "FP-CP2104-F03-GMR-MFG")
      (description "IC SGL USB-TO-UART BRIDGE 24QFN")
      (fields
        (field (name "OCTOPART") "https://octopart.com/cp2104-f03-gmr-silicon+labs-19668642")
        (field (name "MANUFACTURER") "Silicon Labs")
      )
      (libsource (lib "myLibs") (part "CMP-08107-000004-1"))
    )
    (comp (ref "U3")
      (value "AXP192")
      (footprint "AXP192")
      (description "Integrated Circuit")
      (libsource (lib "myLibs") (part "AXP192"))
    )
    (comp (ref "U4")
      (value "SY7088")
      (footprint "SY7088")
      (description "LED")
      (fields (field (name "MANUFACTURER_PART_NUMBER") "SY7088DGC"))
      (libsource (lib "myLibs") (part "SY7088DGC"))
    )
    (comp (ref "U5")
      (value "ESP-PSRAM64H")
      (footprint "ESP-PSRAM64H")
      (description "64 Mbit serial pseudo SRAM")
      (libsource (lib "myLibs") (part "ESP-PSRAM64H"))
    )
    (comp (ref "U6")
      (value "MAX98357AETE+T")
      (footprint "FP-T1633-4-MFG")
      (description "IC AMP CLASS D MONO 3.2W 16TQFN")
      (fields (field (name "MANUFACTURER") "Maxim"))
      (libsource (lib "myLibs") (part "CMP-05698-000018-1"))
    )
    (comp (ref "u7")
      (value "SPI_Flash")
      (footprint "SPI_Flash_MT25QL128ABA1ESE-0SIT")
      (description "3V 128M-BIT\r\nSERIAL NOR FLASH MEMORY")
      (libsource (lib "myLibs") (part "SPI_Flash_MT25QL128ABA1ESE-0SIT"))
    )
    (comp (ref "U8")
      (value "PCF8563")
      (footprint "FP-SOT96-1-MFG")
      (description "IC RTC CLK/CALENDAR I2C 8-SOIC")
      (fields
        (field (name "OCTOPART") "https://octopart.com/pcf8563t%2Ff4%2C118-nxp+semiconductors-10476398")
        (field (name "MANUFACTURER") "NXP Semiconductors")
      )
      (libsource (lib "myLibs") (part "CMP-10083-000003-1"))
    )
    (comp (ref "USB_C1")
      (value "TypeC_cntr")
      (footprint "TypeC")
      (description "Generic typeC connector")
      (libsource (lib "myLibs") (part "TypeC_cntr"))
    )
    (comp (ref "X1")
      (value "32.768K")
      (footprint "FP-ABS06-MFG")
      (description "Crystal 32.768kHz ±10ppm (Tol) 9pF FUND 90kΩ 2-Pin Mini-CSMD T/R")
      (fields (field (name "TOLERANCE") "10ppm") (field (name "MANUFACTURER") "Abracon"))
      (libsource (lib "myLibs") (part "CMP-27762-003430-2"))
    )
    (comp (ref "X2")
      (value "40Mhz")
      (footprint "FP-ABM8-MFG")
      (description "Crystal 40MHz ±10ppm 10pF SMD-4 3.2mm x 2.5mm")
      (fields (field (name "TOLERANCE") "10ppm") (field (name "MANUFACTURER") "Abracon"))
      (libsource (lib "myLibs") (part "CMP-27762-008947-1"))
    )
  )
  (nets
    (net (code "1") (name "/BST_EN") (class "Default")
      (node (ref "R25") (pin "1") (pinfunction "1_1") (pintype "passive"))
      (node (ref "U3") (pin "40") (pinfunction "EXTEN_40") (pintype "passive"))
    )
    (net (code "2") (name "/BUS_PW_EN") (class "Default")
      (node (ref "C25") (pin "1") (pinfunction "1_1") (pintype "passive"))
      (node (ref "R7") (pin "2") (pinfunction "2_2") (pintype "passive"))
      (node (ref "U3") (pin "19") (pinfunction "GPIO0_19") (pintype "passive"))
      (node (ref "U3") (pin "6") (pinfunction "N_VBUSEN_6") (pintype "passive"))
    )
    (net (code "3") (name "/CP_D_N") (class "Default")
      (node (ref "D8") (pin "3") (pinfunction "I/O_2_3") (pintype "bidirectional"))
      (node (ref "R49") (pin "2") (pinfunction "2_2") (pintype "passive"))
      (node (ref "U2") (pin "4") (pinfunction "D-_4") (pintype "bidirectional"))
    )
    (net (code "4") (name "/CP_D_P") (class "Default")
      (node (ref "D8") (pin "1") (pinfunction "I/O_1_1") (pintype "bidirectional"))
      (node (ref "R47") (pin "2") (pinfunction "2_2") (pintype "passive"))
      (node (ref "U2") (pin "3") (pinfunction "D+_3") (pintype "bidirectional"))
    )
    (net (code "5") (name "/CP_RX") (class "Default")
      (node (ref "R12") (pin "1") (pinfunction "1_1") (pintype "passive"))
      (node (ref "U2") (pin "20") (pinfunction "RXD_20") (pintype "input"))
    )
    (net (code "6") (name "/CP_TX") (class "Default")
      (node (ref "R10") (pin "1") (pinfunction "1_1") (pintype "passive"))
      (node (ref "U2") (pin "21") (pinfunction "TXD_21") (pintype "output"))
    )
    (net (code "7") (name "/EXT_G0") (class "Default")
      (node (ref "J1") (pin "24") (pinfunction "24_24") (pintype "passive"))
      (node (ref "R50") (pin "1") (pinfunction "1_1") (pintype "passive"))
    )
    (net (code "8") (name "/EXT_G1") (class "Default")
      (node (ref "J1") (pin "14") (pinfunction "14_14") (pintype "passive"))
      (node (ref "R20") (pin "1") (pinfunction "1_1") (pintype "passive"))
    )
    (net (code "9") (name "/EXT_G2") (class "Default")
      (node (ref "J1") (pin "23") (pinfunction "23_23") (pintype "passive"))
      (node (ref "R48") (pin "1") (pinfunction "1_1") (pintype "passive"))
    )
    (net (code "10") (name "/EXT_G3") (class "Default")
      (node (ref "J1") (pin "13") (pinfunction "13_13") (pintype "passive"))
      (node (ref "R45") (pin "1") (pinfunction "1_1") (pintype "passive"))
    )
    (net (code "11") (name "/EXT_G13") (class "Default")
      (node (ref "J1") (pin "15") (pinfunction "15_15") (pintype "passive"))
      (node (ref "R24") (pin "1") (pinfunction "1_1") (pintype "passive"))
    )
    (net (code "12") (name "/EXT_G14") (class "Default")
      (node (ref "J1") (pin "16") (pinfunction "16_16") (pintype "passive"))
      (node (ref "R28") (pin "1") (pinfunction "1_1") (pintype "passive"))
    )
    (net (code "13") (name "/EXT_G18") (class "Default")
      (node (ref "J1") (pin "11") (pinfunction "11_11") (pintype "passive"))
      (node (ref "R42") (pin "1") (pinfunction "1_1") (pintype "passive"))
    )
    (net (code "14") (name "/EXT_G19") (class "Default")
      (node (ref "J1") (pin "22") (pinfunction "22_22") (pintype "passive"))
      (node (ref "R46") (pin "1") (pinfunction "1_1") (pintype "passive"))
    )
    (net (code "15") (name "/EXT_G21") (class "Default")
      (node (ref "J1") (pin "17") (pinfunction "17_17") (pintype "passive"))
      (node (ref "R30") (pin "1") (pinfunction "1_1") (pintype "passive"))
    )
    (net (code "16") (name "/EXT_G22") (class "Default")
      (node (ref "J1") (pin "18") (pinfunction "18_18") (pintype "passive"))
      (node (ref "R31") (pin "1") (pinfunction "1_1") (pintype "passive"))
    )
    (net (code "17") (name "/EXT_G23") (class "Default")
      (node (ref "J1") (pin "7") (pinfunction "7_7") (pintype "passive"))
      (node (ref "R27") (pin "1") (pinfunction "1_1") (pintype "passive"))
    )
    (net (code "18") (name "/EXT_G25") (class "Default")
      (node (ref "J1") (pin "8") (pinfunction "8_8") (pintype "passive"))
      (node (ref "R29") (pin "1") (pinfunction "1_1") (pintype "passive"))
    )
    (net (code "19") (name "/EXT_G26") (class "Default")
      (node (ref "J1") (pin "10") (pinfunction "10_10") (pintype "passive"))
      (node (ref "R34") (pin "1") (pinfunction "1_1") (pintype "passive"))
    )
    (net (code "20") (name "/EXT_G27") (class "Default")
      (node (ref "J1") (pin "21") (pinfunction "21_21") (pintype "passive"))
      (node (ref "R44") (pin "1") (pinfunction "1_1") (pintype "passive"))
    )
    (net (code "21") (name "/EXT_G32") (class "Default")
      (node (ref "J1") (pin "19") (pinfunction "19_19") (pintype "passive"))
      (node (ref "J4") (pin "1") (pinfunction "1_1") (pintype "passive"))
      (node (ref "R33") (pin "1") (pinfunction "1_1") (pintype "passive"))
    )
    (net (code "22") (name "/EXT_G33") (class "Default")
      (node (ref "J1") (pin "20") (pinfunction "20_20") (pintype "passive"))
      (node (ref "J4") (pin "2") (pinfunction "2_2") (pintype "passive"))
      (node (ref "R41") (pin "1") (pinfunction "1_1") (pintype "passive"))
    )
    (net (code "23") (name "/EXT_G34") (class "Default")
      (node (ref "J1") (pin "26") (pinfunction "26_26") (pintype "passive"))
      (node (ref "R52") (pin "1") (pinfunction "1_1") (pintype "passive"))
    )
    (net (code "24") (name "/EXT_G35") (class "Default")
      (node (ref "J1") (pin "2") (pinfunction "2_2") (pintype "passive"))
      (node (ref "R18") (pin "1") (pinfunction "1_1") (pintype "passive"))
    )
    (net (code "25") (name "/EXT_G36") (class "Default")
      (node (ref "J1") (pin "4") (pinfunction "4_4") (pintype "passive"))
      (node (ref "R22") (pin "1") (pinfunction "1_1") (pintype "passive"))
    )
    (net (code "26") (name "/EXT_G38") (class "Default")
      (node (ref "J1") (pin "9") (pinfunction "9_9") (pintype "passive"))
      (node (ref "R32") (pin "1") (pinfunction "1_1") (pintype "passive"))
    )
    (net (code "27") (name "/EXT_RST") (class "Default")
      (node (ref "J1") (pin "6") (pinfunction "6_6") (pintype "passive"))
      (node (ref "R51") (pin "1") (pinfunction "1_1") (pintype "passive"))
    )
    (net (code "28") (name "/GPIO0") (class "Default")
      (node (ref "D1") (pin "1") (pinfunction "K_1") (pintype "passive"))
      (node (ref "D7") (pin "3") (pinfunction "I/O_2_3") (pintype "bidirectional"))
      (node (ref "Q1") (pin "3") (pinfunction "C_3") (pintype "passive"))
      (node (ref "R50") (pin "2") (pinfunction "2_2") (pintype "passive"))
      (node (ref "U1") (pin "23") (pinfunction "GPIO0_23") (pintype "bidirectional"))
      (node (ref "U6") (pin "14") (pinfunction "LRCLK_14") (pintype "input"))
    )
    (net (code "29") (name "/GPIO1") (class "Default")
      (node (ref "D3") (pin "6") (pinfunction "I/O_4_6") (pintype "bidirectional"))
      (node (ref "R12") (pin "2") (pinfunction "2_2") (pintype "passive"))
      (node (ref "R20") (pin "2") (pinfunction "2_2") (pintype "passive"))
      (node (ref "U1") (pin "41") (pinfunction "U0TXD_41") (pintype "bidirectional"))
    )
    (net (code "30") (name "/GPIO2") (class "Default")
      (node (ref "D7") (pin "1") (pinfunction "I/O_1_1") (pintype "bidirectional"))
      (node (ref "R48") (pin "2") (pinfunction "2_2") (pintype "passive"))
      (node (ref "U1") (pin "22") (pinfunction "GPIO2_22") (pintype "bidirectional"))
      (node (ref "U6") (pin "1") (pinfunction "DIN_1") (pintype "input"))
    )
    (net (code "31") (name "/GPIO3") (class "Default")
      (node (ref "D5") (pin "4") (pinfunction "I/O_3_4") (pintype "bidirectional"))
      (node (ref "R10") (pin "2") (pinfunction "2_2") (pintype "passive"))
      (node (ref "R45") (pin "2") (pinfunction "2_2") (pintype "passive"))
      (node (ref "U1") (pin "40") (pinfunction "U0RXD_40") (pintype "bidirectional"))
    )
    (net (code "32") (name "/GPIO4") (class "Default")
      (node (ref "CD1") (pin "2") (pinfunction "CD/DAT3_2") (pintype "passive"))
      (node (ref "R15") (pin "1") (pinfunction "1_1") (pintype "passive"))
      (node (ref "U1") (pin "24") (pinfunction "GPIO4_24") (pintype "bidirectional"))
    )
    (net (code "33") (name "/GPIO5") (class "Default")
      (node (ref "J2") (pin "5") (pinfunction "5_5") (pintype "passive"))
      (node (ref "U1") (pin "34") (pinfunction "GPIO5_34") (pintype "bidirectional"))
    )
    (net (code "34") (name "/GPIO6") (class "Default")
      (node (ref "U1") (pin "31") (pinfunction "SD_CLK_31") (pintype "bidirectional"))
      (node (ref "u7") (pin "6") (pinfunction "SCLK_6") (pintype "passive"))
    )
    (net (code "35") (name "/GPIO7") (class "Default")
      (node (ref "U1") (pin "32") (pinfunction "SD_DATA_0_32") (pintype "bidirectional"))
      (node (ref "U5") (pin "2") (pinfunction "SO/SIO1_2") (pintype "passive"))
      (node (ref "u7") (pin "2") (pinfunction "SO_2") (pintype "passive"))
    )
    (net (code "36") (name "/GPIO8") (class "Default")
      (node (ref "U1") (pin "33") (pinfunction "SD_DATA_1_33") (pintype "bidirectional"))
      (node (ref "U5") (pin "5") (pinfunction "SI/SIO0_5") (pintype "passive"))
      (node (ref "u7") (pin "5") (pinfunction "SI_5") (pintype "passive"))
    )
    (net (code "37") (name "/GPIO9") (class "Default")
      (node (ref "U1") (pin "28") (pinfunction "SD_DATA_2_28") (pintype "bidirectional"))
      (node (ref "U5") (pin "7") (pinfunction "SIO3_7") (pintype "passive"))
      (node (ref "u7") (pin "7") (pinfunction "HOLD#_7") (pintype "passive"))
    )
    (net (code "38") (name "/GPIO10") (class "Default")
      (node (ref "U1") (pin "29") (pinfunction "SD_DATA_3_29") (pintype "bidirectional"))
      (node (ref "U5") (pin "3") (pinfunction "SIO2_3") (pintype "passive"))
      (node (ref "u7") (pin "3") (pinfunction "WP#_3") (pintype "passive"))
    )
    (net (code "39") (name "/GPIO11") (class "Default")
      (node (ref "U1") (pin "30") (pinfunction "SD_CMD_30") (pintype "bidirectional"))
      (node (ref "u7") (pin "1") (pinfunction "CS_1") (pintype "passive"))
    )
    (net (code "40") (name "/GPIO12") (class "Default")
      (node (ref "U1") (pin "18") (pinfunction "MTDI_18") (pintype "bidirectional"))
      (node (ref "U6") (pin "16") (pinfunction "BCLK_16") (pintype "input"))
    )
    (net (code "41") (name "/GPIO13") (class "Default")
      (node (ref "D3") (pin "1") (pinfunction "I/O_1_1") (pintype "bidirectional"))
      (node (ref "R24") (pin "2") (pinfunction "2_2") (pintype "passive"))
      (node (ref "U1") (pin "20") (pinfunction "MTCK_20") (pintype "bidirectional"))
    )
    (net (code "42") (name "/GPIO14") (class "Default")
      (node (ref "D3") (pin "3") (pinfunction "I/O_2_3") (pintype "bidirectional"))
      (node (ref "R28") (pin "2") (pinfunction "2_2") (pintype "passive"))
      (node (ref "U1") (pin "17") (pinfunction "MTMS_17") (pintype "bidirectional"))
    )
    (net (code "43") (name "/GPIO15") (class "Default")
      (node (ref "J2") (pin "7") (pinfunction "7_7") (pintype "passive"))
      (node (ref "U1") (pin "21") (pinfunction "MTDO_21") (pintype "bidirectional"))
    )
    (net (code "44") (name "/GPIO16") (class "Default")
      (node (ref "R43") (pin "2") (pinfunction "2_2") (pintype "passive"))
      (node (ref "U1") (pin "25") (pinfunction "GPIO16_25") (pintype "bidirectional"))
      (node (ref "U5") (pin "1") (pinfunction "CS_1") (pintype "passive"))
    )
    (net (code "45") (name "/GPIO17") (class "Default")
      (node (ref "U1") (pin "27") (pinfunction "GPIO17_27") (pintype "bidirectional"))
      (node (ref "U5") (pin "6") (pinfunction "SCLK_6") (pintype "passive"))
    )
    (net (code "46") (name "/GPIO18") (class "Default")
      (node (ref "CD1") (pin "5") (pinfunction "CLK_5") (pintype "passive"))
      (node (ref "D5") (pin "3") (pinfunction "I/O_2_3") (pintype "bidirectional"))
      (node (ref "R17") (pin "1") (pinfunction "1_1") (pintype "passive"))
      (node (ref "R38") (pin "2") (pinfunction "2_2") (pintype "passive"))
      (node (ref "R42") (pin "2") (pinfunction "2_2") (pintype "passive"))
      (node (ref "U1") (pin "35") (pinfunction "GPIO18_35") (pintype "bidirectional"))
    )
    (net (code "47") (name "/GPIO19") (class "Default")
      (node (ref "D7") (pin "6") (pinfunction "I/O_4_6") (pintype "bidirectional"))
      (node (ref "R46") (pin "2") (pinfunction "2_2") (pintype "passive"))
      (node (ref "U1") (pin "38") (pinfunction "GPIO19_38") (pintype "bidirectional"))
    )
    (net (code "48") (name "/GPIO21") (class "Default")
      (node (ref "D3") (pin "4") (pinfunction "I/O_3_4") (pintype "bidirectional"))
      (node (ref "J3") (pin "3") (pinfunction "3_3") (pintype "passive"))
      (node (ref "R30") (pin "2") (pinfunction "2_2") (pintype "passive"))
      (node (ref "R55") (pin "2") (pinfunction "2_2") (pintype "passive"))
      (node (ref "U1") (pin "42") (pinfunction "GPIO21_42") (pintype "bidirectional"))
      (node (ref "U3") (pin "1") (pinfunction "SDA_1") (pintype "passive"))
      (node (ref "U8") (pin "5") (pinfunction "SDA_5") (pintype "bidirectional"))
    )
    (net (code "49") (name "/GPIO22") (class "Default")
      (node (ref "D4") (pin "6") (pinfunction "I/O_4_6") (pintype "bidirectional"))
      (node (ref "J3") (pin "4") (pinfunction "4_4") (pintype "passive"))
      (node (ref "R31") (pin "2") (pinfunction "2_2") (pintype "passive"))
      (node (ref "R57") (pin "2") (pinfunction "2_2") (pintype "passive"))
      (node (ref "U1") (pin "39") (pinfunction "GPIO22_39") (pintype "bidirectional"))
      (node (ref "U3") (pin "2") (pinfunction "SCK_2") (pintype "passive"))
      (node (ref "U8") (pin "6") (pinfunction "SCL_6") (pintype "input"))
    )
    (net (code "50") (name "/GPIO23") (class "Default")
      (node (ref "CD1") (pin "3") (pinfunction "CMD_3") (pintype "passive"))
      (node (ref "D2") (pin "3") (pinfunction "I/O_2_3") (pintype "bidirectional"))
      (node (ref "R16") (pin "1") (pinfunction "1_1") (pintype "passive"))
      (node (ref "R27") (pin "2") (pinfunction "2_2") (pintype "passive"))
      (node (ref "R36") (pin "2") (pinfunction "2_2") (pintype "passive"))
      (node (ref "U1") (pin "36") (pinfunction "GPIO23_36") (pintype "bidirectional"))
    )
    (net (code "51") (name "/GPIO25") (class "Default")
      (node (ref "D2") (pin "4") (pinfunction "I/O_3_4") (pintype "bidirectional"))
      (node (ref "R29") (pin "2") (pinfunction "2_2") (pintype "passive"))
      (node (ref "U1") (pin "14") (pinfunction "GPIO25_14") (pintype "bidirectional"))
    )
    (net (code "52") (name "/GPIO26") (class "Default")
      (node (ref "D5") (pin "1") (pinfunction "I/O_1_1") (pintype "bidirectional"))
      (node (ref "R34") (pin "2") (pinfunction "2_2") (pintype "passive"))
      (node (ref "U1") (pin "15") (pinfunction "GPIO26_15") (pintype "bidirectional"))
    )
    (net (code "53") (name "/GPIO27") (class "Default")
      (node (ref "D4") (pin "4") (pinfunction "I/O_3_4") (pintype "bidirectional"))
      (node (ref "R44") (pin "2") (pinfunction "2_2") (pintype "passive"))
      (node (ref "U1") (pin "16") (pinfunction "GPIO27_16") (pintype "bidirectional"))
    )
    (net (code "54") (name "/GPIO32") (class "Default")
      (node (ref "D4") (pin "1") (pinfunction "I/O_1_1") (pintype "bidirectional"))
      (node (ref "R33") (pin "2") (pinfunction "2_2") (pintype "passive"))
      (node (ref "R56") (pin "2") (pinfunction "2_2") (pintype "passive"))
      (node (ref "U1") (pin "12") (pinfunction "32K_XP_12") (pintype "bidirectional"))
    )
    (net (code "55") (name "/GPIO33") (class "Default")
      (node (ref "D4") (pin "3") (pinfunction "I/O_2_3") (pintype "bidirectional"))
      (node (ref "R41") (pin "2") (pinfunction "2_2") (pintype "passive"))
      (node (ref "R54") (pin "2") (pinfunction "2_2") (pintype "passive"))
      (node (ref "U1") (pin "13") (pinfunction "32K_XN_13") (pintype "bidirectional"))
    )
    (net (code "56") (name "/GPIO34") (class "Default")
      (node (ref "D7") (pin "4") (pinfunction "I/O_3_4") (pintype "bidirectional"))
      (node (ref "R52") (pin "2") (pinfunction "2_2") (pintype "passive"))
      (node (ref "U1") (pin "10") (pinfunction "VDET_1_10") (pintype "input"))
    )
    (net (code "57") (name "/GPIO35") (class "Default")
      (node (ref "D2") (pin "6") (pinfunction "I/O_4_6") (pintype "bidirectional"))
      (node (ref "R18") (pin "2") (pinfunction "2_2") (pintype "passive"))
      (node (ref "U1") (pin "11") (pinfunction "VDET_2_11") (pintype "input"))
    )
    (net (code "58") (name "/GPIO36") (class "Default")
      (node (ref "D2") (pin "1") (pinfunction "I/O_1_1") (pintype "bidirectional"))
      (node (ref "R22") (pin "2") (pinfunction "2_2") (pintype "passive"))
      (node (ref "U1") (pin "5") (pinfunction "SENSOR_VP_5") (pintype "input"))
    )
    (net (code "59") (name "/GPIO38") (class "Default")
      (node (ref "CD1") (pin "7") (pinfunction "DAT0_7") (pintype "passive"))
      (node (ref "D5") (pin "6") (pinfunction "I/O_4_6") (pintype "bidirectional"))
      (node (ref "R19") (pin "1") (pinfunction "1_1") (pintype "passive"))
      (node (ref "R32") (pin "2") (pinfunction "2_2") (pintype "passive"))
      (node (ref "R37") (pin "2") (pinfunction "2_2") (pintype "passive"))
      (node (ref "U1") (pin "7") (pinfunction "SENSOR_CAPN_7") (pintype "input"))
    )
    (net (code "60") (name "/GPIO39") (class "Default")
      (node (ref "J3") (pin "5") (pinfunction "5_5") (pintype "passive"))
      (node (ref "U1") (pin "8") (pinfunction "SENSOR_VN_8") (pintype "input"))
    )
    (net (code "61") (name "/LCD_BL") (class "Default")
      (node (ref "J2") (pin "9") (pinfunction "9_9") (pintype "passive"))
      (node (ref "R14") (pin "2") (pinfunction "2_2") (pintype "passive"))
    )
    (net (code "62") (name "/LCD_BL_TP") (class "Default")
      (node (ref "C37") (pin "1") (pinfunction "1_1") (pintype "passive"))
      (node (ref "L3") (pin "1") (pinfunction "1_1") (pintype "passive"))
      (node (ref "R14") (pin "1") (pinfunction "1_1") (pintype "passive"))
      (node (ref "U3") (pin "17") (pinfunction "DCDC3_17") (pintype "passive"))
    )
    (net (code "63") (name "/LCD_RST") (class "Default")
      (node (ref "J2") (pin "6") (pinfunction "6_6") (pintype "passive"))
      (node (ref "J3") (pin "6") (pinfunction "6_6") (pintype "passive"))
      (node (ref "R40") (pin "2") (pinfunction "2_2") (pintype "passive"))
      (node (ref "U3") (pin "42") (pinfunction "GPIO4_42") (pintype "passive"))
    )
    (net (code "64") (name "/LNA_IN") (class "Default")
      (node (ref "C12") (pin "1") (pinfunction "1_1") (pintype "passive"))
      (node (ref "L1") (pin "1") (pinfunction "1_1") (pintype "passive"))
      (node (ref "U1") (pin "2") (pinfunction "LNA_IN_2") (pintype "bidirectional"))
    )
    (net (code "65") (name "/MCU_RST") (class "Default")
      (node (ref "C27") (pin "2") (pinfunction "2_2") (pintype "passive"))
      (node (ref "D8") (pin "6") (pinfunction "I/O_4_6") (pintype "bidirectional"))
      (node (ref "Q2") (pin "3") (pinfunction "C_3") (pintype "passive"))
      (node (ref "R11") (pin "2") (pinfunction "2_2") (pintype "passive"))
      (node (ref "R51") (pin "2") (pinfunction "2_2") (pintype "passive"))
      (node (ref "SW1") (pin "2") (pinfunction "2_2") (pintype "passive"))
      (node (ref "U1") (pin "9") (pinfunction "CHIP_PU_9") (pintype "input"))
      (node (ref "U3") (pin "5") (pinfunction "PWROK_5") (pintype "passive"))
    )
    (net (code "66") (name "/OSCI") (class "Default")
      (node (ref "C57") (pin "1") (pinfunction "1_1") (pintype "passive"))
      (node (ref "U8") (pin "1") (pinfunction "OSCI_1") (pintype "input"))
      (node (ref "X1") (pin "1") (pinfunction "1_1") (pintype "passive"))
    )
    (net (code "67") (name "/PWR_KEY") (class "Default")
      (node (ref "C54") (pin "1") (pinfunction "1_1") (pintype "passive"))
      (node (ref "SW2") (pin "2") (pinfunction "2_2") (pintype "passive"))
      (node (ref "TP7") (pin "1") (pinfunction "TP_1") (pintype "passive"))
      (node (ref "U3") (pin "23") (pinfunction "PWRON_23") (pintype "passive"))
    )
    (net (code "68") (name "/RTC_BAT") (class "Default")
      (node (ref "BT1") (pin "1") (pinfunction "+_1") (pintype "passive"))
      (node (ref "C24") (pin "2") (pinfunction "2_2") (pintype "passive"))
      (node (ref "U3") (pin "30") (pinfunction "BACKUP_30") (pintype "passive"))
    )
    (net (code "69") (name "/SPK_EN") (class "Default")
      (node (ref "R39") (pin "2") (pinfunction "2_2") (pintype "passive"))
      (node (ref "U3") (pin "20") (pinfunction "GPIO2_20") (pintype "passive"))
      (node (ref "U6") (pin "4") (pinfunction "~{SD_MODE}_4") (pintype "input"))
    )
    (net (code "70") (name "/SYS_LED") (class "Default")
      (node (ref "R59") (pin "1") (pinfunction "1_1") (pintype "passive"))
      (node (ref "R60") (pin "1") (pinfunction "1_1") (pintype "passive"))
      (node (ref "U3") (pin "18") (pinfunction "GPIO1_18") (pintype "passive"))
    )
    (net (code "71") (name "/USB_N") (class "Default")
      (node (ref "R49") (pin "1") (pinfunction "1_1") (pintype "passive"))
      (node (ref "USB_C1") (pin "A7") (pinfunction "DN1_A7") (pintype "passive"))
      (node (ref "USB_C1") (pin "B7") (pinfunction "DN2_B7") (pintype "passive"))
    )
    (net (code "72") (name "/USB_P") (class "Default")
      (node (ref "R47") (pin "1") (pinfunction "1_1") (pintype "passive"))
      (node (ref "USB_C1") (pin "A6") (pinfunction "DP1_A6") (pintype "passive"))
      (node (ref "USB_C1") (pin "B6") (pinfunction "DP2_B6") (pintype "passive"))
    )
    (net (code "73") (name "/VDD_SDIO") (class "Default")
      (node (ref "C14") (pin "2") (pinfunction "2_2") (pintype "passive"))
      (node (ref "U1") (pin "26") (pinfunction "VDD_SDIO_26") (pintype "power_in"))
    )
    (net (code "74") (name "/VIB_MOTOR") (class "Default")
      (node (ref "C30") (pin "2") (pinfunction "2_2") (pintype "passive"))
      (node (ref "R58") (pin "1") (pinfunction "1_1") (pintype "passive"))
      (node (ref "U3") (pin "11") (pinfunction "LDO3_11") (pintype "passive"))
    )
    (net (code "75") (name "/XTAL P") (class "Default")
      (node (ref "R6") (pin "2") (pinfunction "2_2") (pintype "passive"))
      (node (ref "U1") (pin "45") (pinfunction "XTAL_P_45") (pintype "input"))
    )
    (net (code "76") (name "BUS_5V") (class "Default")
      (node (ref "C23") (pin "1") (pinfunction "1_1") (pintype "passive"))
      (node (ref "C42") (pin "2") (pinfunction "2_2") (pintype "passive"))
      (node (ref "C44") (pin "1") (pinfunction "1_1") (pintype "passive"))
      (node (ref "J1") (pin "28") (pinfunction "28_28") (pintype "passive"))
      (node (ref "J4") (pin "3") (pinfunction "3_3") (pintype "passive"))
      (node (ref "R21") (pin "1") (pinfunction "1_1") (pintype "passive"))
      (node (ref "U3") (pin "31") (pinfunction "VBUS_31") (pintype "passive"))
      (node (ref "U4") (pin "7") (pinfunction "OUT_1_7") (pintype "passive"))
      (node (ref "U4") (pin "8") (pinfunction "OUT_2_8") (pintype "passive"))
    )
    (net (code "77") (name "GND") (class "Default")
      (node (ref "ANT1") (pin "2") (pinfunction "GND_2") (pintype "passive"))
      (node (ref "BT1") (pin "2") (pinfunction "-_2") (pintype "passive"))
      (node (ref "C1") (pin "1") (pinfunction "1_1") (pintype "passive"))
      (node (ref "C10") (pin "1") (pinfunction "1_1") (pintype "passive"))
      (node (ref "C11") (pin "2") (pinfunction "2_2") (pintype "passive"))
      (node (ref "C12") (pin "2") (pinfunction "2_2") (pintype "passive"))
      (node (ref "C13") (pin "2") (pinfunction "2_2") (pintype "passive"))
      (node (ref "C14") (pin "1") (pinfunction "1_1") (pintype "passive"))
      (node (ref "C15") (pin "1") (pinfunction "1_1") (pintype "passive"))
      (node (ref "C16") (pin "1") (pinfunction "1_1") (pintype "passive"))
      (node (ref "C17") (pin "1") (pinfunction "1_1") (pintype "passive"))
      (node (ref "C18") (pin "2") (pinfunction "2_2") (pintype "passive"))
      (node (ref "C19") (pin "2") (pinfunction "2_2") (pintype "passive"))
      (node (ref "C2") (pin "2") (pinfunction "2_2") (pintype "passive"))
      (node (ref "C20") (pin "2") (pinfunction "2_2") (pintype "passive"))
      (node (ref "C21") (pin "2") (pinfunction "2_2") (pintype "passive"))
      (node (ref "C22") (pin "2") (pinfunction "2_2") (pintype "passive"))
      (node (ref "C23") (pin "2") (pinfunction "2_2") (pintype "passive"))
      (node (ref "C24") (pin "1") (pinfunction "1_1") (pintype "passive"))
      (node (ref "C25") (pin "2") (pinfunction "2_2") (pintype "passive"))
      (node (ref "C26") (pin "2") (pinfunction "2_2") (pintype "passive"))
      (node (ref "C27") (pin "1") (pinfunction "1_1") (pintype "passive"))
      (node (ref "C29") (pin "1") (pinfunction "1_1") (pintype "passive"))
      (node (ref "C3") (pin "1") (pinfunction "1_1") (pintype "passive"))
      (node (ref "C30") (pin "1") (pinfunction "1_1") (pintype "passive"))
      (node (ref "C31") (pin "2") (pinfunction "2_2") (pintype "passive"))
      (node (ref "C32") (pin "2") (pinfunction "2_2") (pintype "passive"))
      (node (ref "C33") (pin "1") (pinfunction "1_1") (pintype "passive"))
      (node (ref "C34") (pin "1") (pinfunction "1_1") (pintype "passive"))
      (node (ref "C35") (pin "1") (pinfunction "1_1") (pintype "passive"))
      (node (ref "C36") (pin "1") (pinfunction "1_1") (pintype "passive"))
      (node (ref "C37") (pin "2") (pinfunction "2_2") (pintype "passive"))
      (node (ref "C38") (pin "2") (pinfunction "2_2") (pintype "passive"))
      (node (ref "C39") (pin "1") (pinfunction "1_1") (pintype "passive"))
      (node (ref "C4") (pin "2") (pinfunction "2_2") (pintype "passive"))
      (node (ref "C40") (pin "2") (pinfunction "2_2") (pintype "passive"))
      (node (ref "C41") (pin "2") (pinfunction "2_2") (pintype "passive"))
      (node (ref "C42") (pin "1") (pinfunction "1_1") (pintype "passive"))
      (node (ref "C43") (pin "2") (pinfunction "2_2") (pintype "passive"))
      (node (ref "C44") (pin "2") (pinfunction "2_2") (pintype "passive"))
      (node (ref "C45") (pin "1") (pinfunction "1_1") (pintype "passive"))
      (node (ref "C46") (pin "2") (pinfunction "2_2") (pintype "passive"))
      (node (ref "C47") (pin "1") (pinfunction "1_1") (pintype "passive"))
      (node (ref "C48") (pin "1") (pinfunction "1_1") (pintype "passive"))
      (node (ref "C49") (pin "2") (pinfunction "2_2") (pintype "passive"))
      (node (ref "C5") (pin "2") (pinfunction "2_2") (pintype "passive"))
      (node (ref "C50") (pin "2") (pinfunction "2_2") (pintype "passive"))
      (node (ref "C51") (pin "1") (pinfunction "1_1") (pintype "passive"))
      (node (ref "C52") (pin "1") (pinfunction "1_1") (pintype "passive"))
      (node (ref "C53") (pin "1") (pinfunction "1_1") (pintype "passive"))
      (node (ref "C55") (pin "2") (pinfunction "2_2") (pintype "passive"))
      (node (ref "C56") (pin "2") (pinfunction "2_2") (pintype "passive"))
      (node (ref "C57") (pin "2") (pinfunction "2_2") (pintype "passive"))
      (node (ref "C6") (pin "1") (pinfunction "1_1") (pintype "passive"))
      (node (ref "C7") (pin "1") (pinfunction "1_1") (pintype "passive"))
      (node (ref "C8") (pin "1") (pinfunction "1_1") (pintype "passive"))
      (node (ref "C9") (pin "2") (pinfunction "2_2") (pintype "passive"))
      (node (ref "CD1") (pin "11") (pinfunction "SHLD_11") (pintype "passive"))
      (node (ref "CD1") (pin "12") (pinfunction "SHLD_12") (pintype "passive"))
      (node (ref "CD1") (pin "13") (pinfunction "SHLD_13") (pintype "passive"))
      (node (ref "CD1") (pin "14") (pinfunction "SHLD_14") (pintype "passive"))
      (node (ref "CD1") (pin "6") (pinfunction "VSS_6") (pintype "passive"))
      (node (ref "D2") (pin "2") (pinfunction "GND_2") (pintype "power_in"))
      (node (ref "D3") (pin "2") (pinfunction "GND_2") (pintype "power_in"))
      (node (ref "D4") (pin "2") (pinfunction "GND_2") (pintype "power_in"))
      (node (ref "D5") (pin "2") (pinfunction "GND_2") (pintype "power_in"))
      (node (ref "D7") (pin "2") (pinfunction "GND_2") (pintype "power_in"))
      (node (ref "D8") (pin "2") (pinfunction "GND_2") (pintype "power_in"))
      (node (ref "D9") (pin "2") (pinfunction "A_2") (pintype "passive"))
      (node (ref "J1") (pin "1") (pinfunction "1_1") (pintype "passive"))
      (node (ref "J1") (pin "3") (pinfunction "3_3") (pintype "passive"))
      (node (ref "J1") (pin "5") (pinfunction "5_5") (pintype "passive"))
      (node (ref "J2") (pin "1") (pinfunction "1_1") (pintype "passive"))
      (node (ref "J2") (pin "10") (pinfunction "10_10") (pintype "passive"))
      (node (ref "J2") (pin "M1") (pinfunction "M1_M1") (pintype "passive"))
      (node (ref "J2") (pin "M2") (pinfunction "M2_M2") (pintype "passive"))
      (node (ref "J3") (pin "2") (pinfunction "2_2") (pintype "passive"))
      (node (ref "J3") (pin "MP1") (pinfunction "MP1_MP1") (pintype "passive"))
      (node (ref "J3") (pin "MP2") (pinfunction "MP2_MP2") (pintype "passive"))
      (node (ref "J4") (pin "4") (pinfunction "4_4") (pintype "passive"))
      (node (ref "J5") (pin "2") (pinfunction "2_2") (pintype "passive"))
      (node (ref "R13") (pin "2") (pinfunction "2_2") (pintype "passive"))
      (node (ref "R23") (pin "2") (pinfunction "2_2") (pintype "passive"))
      (node (ref "R26") (pin "2") (pinfunction "2_2") (pintype "passive"))
      (node (ref "R4") (pin "2") (pinfunction "2_2") (pintype "passive"))
      (node (ref "R5") (pin "2") (pinfunction "2_2") (pintype "passive"))
      (node (ref "R7") (pin "1") (pinfunction "1_1") (pintype "passive"))
      (node (ref "SW1") (pin "3") (pinfunction "3_3") (pintype "passive"))
      (node (ref "SW2") (pin "1") (pinfunction "1_1") (pintype "passive"))
      (node (ref "TP1") (pin "1") (pinfunction "TP_1") (pintype "passive"))
      (node (ref "U1") (pin "49") (pinfunction "GND_49") (pintype "power_in"))
      (node (ref "U2") (pin "2") (pinfunction "GND_2") (pintype "power_in"))
      (node (ref "U2") (pin "25") (pinfunction "GND_25") (pintype "power_in"))
      (node (ref "U3") (pin "16") (pinfunction "PGND3_16") (pintype "passive"))
      (node (ref "U3") (pin "22") (pinfunction "AGND_22") (pintype "passive"))
      (node (ref "U3") (pin "37") (pinfunction "TS_37") (pintype "passive"))
      (node (ref "U3") (pin "4") (pinfunction "N_OE_4") (pintype "passive"))
      (node (ref "U3") (pin "46") (pinfunction "PGND1_46") (pintype "passive"))
      (node (ref "U3") (pin "49") (pinfunction "EP_49") (pintype "passive"))
      (node (ref "U3") (pin "9") (pinfunction "PGND2_9") (pintype "passive"))
      (node (ref "U4") (pin "4") (pinfunction "SGND_4") (pintype "passive"))
      (node (ref "U4") (pin "9") (pinfunction "PGND_9") (pintype "passive"))
      (node (ref "U5") (pin "4") (pinfunction "GND_4") (pintype "passive"))
      (node (ref "U6") (pin "11") (pinfunction "GND_11") (pintype "power_in"))
      (node (ref "U6") (pin "15") (pinfunction "GND_15") (pintype "power_in"))
      (node (ref "U6") (pin "17") (pinfunction "EP_17") (pintype "passive"))
      (node (ref "U6") (pin "2") (pinfunction "GAIN_SLOT_2") (pintype "passive"))
      (node (ref "U6") (pin "3") (pinfunction "GND_3") (pintype "power_in"))
      (node (ref "U8") (pin "4") (pinfunction "VSS_4") (pintype "power_in"))
      (node (ref "USB_C1") (pin "A1") (pinfunction "GND_A1") (pintype "passive"))
      (node (ref "USB_C1") (pin "A12") (pinfunction "Shell_A12") (pintype "passive"))
      (node (ref "X2") (pin "2") (pinfunction "GND_2") (pintype "power_in"))
      (node (ref "X2") (pin "4") (pinfunction "GND_4") (pintype "power_in"))
      (node (ref "p2") (pin "2") (pinfunction "2_2") (pintype "passive"))
      (node (ref "u7") (pin "4") (pinfunction "GND_4") (pintype "passive"))
    )
    (net (code "78") (name "IPS_BUS") (class "Default")
      (node (ref "C11") (pin "1") (pinfunction "1_1") (pintype "passive"))
      (node (ref "C2") (pin "1") (pinfunction "1_1") (pintype "passive"))
      (node (ref "C36") (pin "2") (pinfunction "2_2") (pintype "passive"))
      (node (ref "C38") (pin "1") (pinfunction "1_1") (pintype "passive"))
      (node (ref "C39") (pin "2") (pinfunction "2_2") (pintype "passive"))
      (node (ref "C4") (pin "1") (pinfunction "1_1") (pintype "passive"))
      (node (ref "C40") (pin "1") (pinfunction "1_1") (pintype "passive"))
      (node (ref "C41") (pin "1") (pinfunction "1_1") (pintype "passive"))
      (node (ref "L4") (pin "1") (pinfunction "1_1") (pintype "passive"))
      (node (ref "R53") (pin "2") (pinfunction "2_2") (pintype "passive"))
      (node (ref "TP4") (pin "1") (pinfunction "TP_1") (pintype "passive"))
      (node (ref "U3") (pin "13") (pinfunction "LDOIN_13") (pintype "passive"))
      (node (ref "U3") (pin "14") (pinfunction "VIN3_14") (pintype "passive"))
      (node (ref "U3") (pin "21") (pinfunction "APS_21") (pintype "passive"))
      (node (ref "U3") (pin "38") (pinfunction "IPSOUT_1_38") (pintype "passive"))
      (node (ref "U3") (pin "39") (pinfunction "IPSOUT_2_39") (pintype "passive"))
      (node (ref "U3") (pin "44") (pinfunction "VIN1_44") (pintype "passive"))
      (node (ref "U3") (pin "7") (pinfunction "VIN2_7") (pintype "passive"))
      (node (ref "U4") (pin "6") (pinfunction "IN_6") (pintype "passive"))
    )
    (net (code "79") (name "MCU_VDD") (class "Default")
      (node (ref "C1") (pin "2") (pinfunction "2_2") (pintype "passive"))
      (node (ref "C10") (pin "2") (pinfunction "2_2") (pintype "passive"))
      (node (ref "C15") (pin "2") (pinfunction "2_2") (pintype "passive"))
      (node (ref "C16") (pin "2") (pinfunction "2_2") (pintype "passive"))
      (node (ref "C17") (pin "2") (pinfunction "2_2") (pintype "passive"))
      (node (ref "C3") (pin "2") (pinfunction "2_2") (pintype "passive"))
      (node (ref "C47") (pin "2") (pinfunction "2_2") (pintype "passive"))
      (node (ref "C48") (pin "2") (pinfunction "2_2") (pintype "passive"))
      (node (ref "C49") (pin "1") (pinfunction "1_1") (pintype "passive"))
      (node (ref "C55") (pin "1") (pinfunction "1_1") (pintype "passive"))
      (node (ref "C6") (pin "2") (pinfunction "2_2") (pintype "passive"))
      (node (ref "C7") (pin "2") (pinfunction "2_2") (pintype "passive"))
      (node (ref "C8") (pin "2") (pinfunction "2_2") (pintype "passive"))
      (node (ref "C9") (pin "1") (pinfunction "1_1") (pintype "passive"))
      (node (ref "D2") (pin "5") (pinfunction "REF_5") (pintype "power_in"))
      (node (ref "D3") (pin "5") (pinfunction "REF_5") (pintype "power_in"))
      (node (ref "D4") (pin "5") (pinfunction "REF_5") (pintype "power_in"))
      (node (ref "D5") (pin "5") (pinfunction "REF_5") (pintype "power_in"))
      (node (ref "D7") (pin "5") (pinfunction "REF_5") (pintype "power_in"))
      (node (ref "D8") (pin "5") (pinfunction "REF_5") (pintype "power_in"))
      (node (ref "J1") (pin "12") (pinfunction "12_12") (pintype "passive"))
      (node (ref "L2") (pin "2") (pinfunction "2_2") (pintype "passive"))
      (node (ref "LED1") (pin "2") (pinfunction "A_2") (pintype "passive"))
      (node (ref "R11") (pin "1") (pinfunction "1_1") (pintype "passive"))
      (node (ref "R2") (pin "1") (pinfunction "1_1") (pintype "passive"))
      (node (ref "R35") (pin "2") (pinfunction "2_2") (pintype "passive"))
      (node (ref "R39") (pin "1") (pinfunction "1_1") (pintype "passive"))
      (node (ref "R43") (pin "1") (pinfunction "1_1") (pintype "passive"))
      (node (ref "R54") (pin "1") (pinfunction "1_1") (pintype "passive"))
      (node (ref "R55") (pin "1") (pinfunction "1_1") (pintype "passive"))
      (node (ref "R56") (pin "1") (pinfunction "1_1") (pintype "passive"))
      (node (ref "R57") (pin "1") (pinfunction "1_1") (pintype "passive"))
      (node (ref "R60") (pin "2") (pinfunction "2_2") (pintype "passive"))
      (node (ref "TP2") (pin "1") (pinfunction "TP_1") (pintype "passive"))
      (node (ref "U1") (pin "1") (pinfunction "VDDA_1") (pintype "power_in"))
      (node (ref "U1") (pin "19") (pinfunction "VDD3P3_RTC_19") (pintype "power_in"))
      (node (ref "U1") (pin "3") (pinfunction "VDD3P3_3") (pintype "power_in"))
      (node (ref "U1") (pin "37") (pinfunction "VDD3P3_CPU_37") (pintype "power_in"))
      (node (ref "U1") (pin "4") (pinfunction "VDD3P3_4") (pintype "power_in"))
      (node (ref "U1") (pin "43") (pinfunction "VDDA_43") (pintype "power_in"))
      (node (ref "U1") (pin "46") (pinfunction "VDDA_46") (pintype "power_in"))
      (node (ref "U3") (pin "47") (pinfunction "DCDC1_47") (pintype "passive"))
      (node (ref "U5") (pin "8") (pinfunction "VCC_8") (pintype "passive"))
      (node (ref "U6") (pin "7") (pinfunction "VDD_7") (pintype "power_in"))
      (node (ref "U6") (pin "8") (pinfunction "VDD_8") (pintype "power_in"))
      (node (ref "u7") (pin "8") (pinfunction "VCC_8") (pintype "passive"))
    )
    (net (code "80") (name "Net-(ANT1-ANT_IN)") (class "Default")
      (node (ref "ANT1") (pin "1") (pinfunction "ANT_IN_1") (pintype "passive"))
      (node (ref "C13") (pin "1") (pinfunction "1_1") (pintype "passive"))
      (node (ref "L1") (pin "2") (pinfunction "2_2") (pintype "passive"))
    )
    (net (code "81") (name "Net-(C26-Pad1)") (class "Default")
      (node (ref "C26") (pin "1") (pinfunction "1_1") (pintype "passive"))
      (node (ref "R6") (pin "1") (pinfunction "1_1") (pintype "passive"))
      (node (ref "X2") (pin "3") (pinfunction "3_3") (pintype "passive"))
    )
    (net (code "82") (name "Net-(C46-Pad1)") (class "Default")
      (node (ref "C46") (pin "1") (pinfunction "1_1") (pintype "passive"))
      (node (ref "J3") (pin "1") (pinfunction "1_1") (pintype "passive"))
      (node (ref "R35") (pin "1") (pinfunction "1_1") (pintype "passive"))
    )
    (net (code "83") (name "Net-(C50-Pad1)") (class "Default")
      (node (ref "C50") (pin "1") (pinfunction "1_1") (pintype "passive"))
      (node (ref "FB1") (pin "2") (pinfunction "2_2") (pintype "passive"))
      (node (ref "p1") (pin "1") (pinfunction "1_1") (pintype "passive"))
    )
    (net (code "84") (name "Net-(C51-Pad2)") (class "Default")
      (node (ref "C51") (pin "2") (pinfunction "2_2") (pintype "passive"))
      (node (ref "FB2") (pin "2") (pinfunction "2_2") (pintype "passive"))
      (node (ref "p1") (pin "2") (pinfunction "2_2") (pintype "passive"))
    )
    (net (code "85") (name "Net-(D1-A)") (class "Default")
      (node (ref "D1") (pin "2") (pinfunction "A_2") (pintype "passive"))
      (node (ref "R2") (pin "2") (pinfunction "2_2") (pintype "passive"))
    )
    (net (code "86") (name "Net-(D9-K)") (class "Default")
      (node (ref "D9") (pin "1") (pinfunction "K_1") (pintype "passive"))
      (node (ref "R58") (pin "2") (pinfunction "2_2") (pintype "passive"))
      (node (ref "p2") (pin "1") (pinfunction "1_1") (pintype "passive"))
    )
    (net (code "87") (name "Net-(J2-Pad2)") (class "Default")
      (node (ref "J2") (pin "2") (pinfunction "2_2") (pintype "passive"))
      (node (ref "R36") (pin "1") (pinfunction "1_1") (pintype "passive"))
    )
    (net (code "88") (name "Net-(J2-Pad3)") (class "Default")
      (node (ref "J2") (pin "3") (pinfunction "3_3") (pintype "passive"))
      (node (ref "R37") (pin "1") (pinfunction "1_1") (pintype "passive"))
    )
    (net (code "89") (name "Net-(J2-Pad4)") (class "Default")
      (node (ref "J2") (pin "4") (pinfunction "4_4") (pintype "passive"))
      (node (ref "R38") (pin "1") (pinfunction "1_1") (pintype "passive"))
    )
    (net (code "90") (name "Net-(LED1-C)") (class "Default")
      (node (ref "LED1") (pin "1") (pinfunction "C_1") (pintype "passive"))
      (node (ref "R59") (pin "2") (pinfunction "2_2") (pintype "passive"))
    )
    (net (code "91") (name "Net-(Q1-B)") (class "Default")
      (node (ref "Q1") (pin "1") (pinfunction "B_1") (pintype "passive"))
      (node (ref "R3") (pin "2") (pinfunction "2_2") (pintype "passive"))
    )
    (net (code "92") (name "Net-(Q1-E)") (class "Default")
      (node (ref "Q1") (pin "2") (pinfunction "E_2") (pintype "passive"))
      (node (ref "R9") (pin "2") (pinfunction "2_2") (pintype "passive"))
      (node (ref "U2") (pin "23") (pinfunction "DTR_23") (pintype "output"))
    )
    (net (code "93") (name "Net-(Q2-B)") (class "Default")
      (node (ref "Q2") (pin "1") (pinfunction "B_1") (pintype "passive"))
      (node (ref "R9") (pin "1") (pinfunction "1_1") (pintype "passive"))
    )
    (net (code "94") (name "Net-(Q2-E)") (class "Default")
      (node (ref "Q2") (pin "2") (pinfunction "E_2") (pintype "passive"))
      (node (ref "R3") (pin "1") (pinfunction "1_1") (pintype "passive"))
      (node (ref "U2") (pin "19") (pinfunction "RTS_19") (pintype "output"))
    )
    (net (code "95") (name "Net-(U1-CAP1)") (class "Default")
      (node (ref "C28") (pin "2") (pinfunction "2_2") (pintype "passive"))
      (node (ref "C34") (pin "2") (pinfunction "2_2") (pintype "passive"))
      (node (ref "R8") (pin "2") (pinfunction "2_2") (pintype "passive"))
      (node (ref "U1") (pin "48") (pinfunction "CAP1_48") (pintype "passive"))
    )
    (net (code "96") (name "Net-(U1-CAP2)") (class "Default")
      (node (ref "C28") (pin "1") (pinfunction "1_1") (pintype "passive"))
      (node (ref "R8") (pin "1") (pinfunction "1_1") (pintype "passive"))
      (node (ref "U1") (pin "47") (pinfunction "CAP2_47") (pintype "passive"))
    )
    (net (code "97") (name "Net-(U1-XTAL_N)") (class "Default")
      (node (ref "C31") (pin "1") (pinfunction "1_1") (pintype "passive"))
      (node (ref "U1") (pin "44") (pinfunction "XTAL_N_44") (pintype "output"))
      (node (ref "X2") (pin "1") (pinfunction "1_1") (pintype "passive"))
    )
    (net (code "98") (name "Net-(U2-VDD)") (class "Default")
      (node (ref "C5") (pin "1") (pinfunction "1_1") (pintype "passive"))
      (node (ref "R1") (pin "1") (pinfunction "1_1") (pintype "passive"))
      (node (ref "U2") (pin "5") (pinfunction "VIO_5") (pintype "bidirectional"))
      (node (ref "U2") (pin "6") (pinfunction "VDD_6") (pintype "power_in"))
    )
    (net (code "99") (name "Net-(U2-~{RST})") (class "Default")
      (node (ref "R1") (pin "2") (pinfunction "2_2") (pintype "passive"))
      (node (ref "U2") (pin "9") (pinfunction "~{RST}_9") (pintype "input"))
    )
    (net (code "100") (name "Net-(U3-BIAS)") (class "Default")
      (node (ref "R13") (pin "1") (pinfunction "1_1") (pintype "passive"))
      (node (ref "U3") (pin "24") (pinfunction "BIAS_24") (pintype "passive"))
    )
    (net (code "101") (name "Net-(U3-LX1)") (class "Default")
      (node (ref "L2") (pin "1") (pinfunction "1_1") (pintype "passive"))
      (node (ref "U3") (pin "45") (pinfunction "LX1_45") (pintype "passive"))
    )
    (net (code "102") (name "Net-(U3-LX3)") (class "Default")
      (node (ref "L3") (pin "2") (pinfunction "2_2") (pintype "passive"))
      (node (ref "U3") (pin "15") (pinfunction "LX3_15") (pintype "passive"))
    )
    (net (code "103") (name "Net-(U3-VINT)") (class "Default")
      (node (ref "C32") (pin "1") (pinfunction "1_1") (pintype "passive"))
      (node (ref "U3") (pin "26") (pinfunction "VINT_26") (pintype "passive"))
    )
    (net (code "104") (name "Net-(U3-VREF)") (class "Default")
      (node (ref "C35") (pin "2") (pinfunction "2_2") (pintype "passive"))
      (node (ref "U3") (pin "25") (pinfunction "VREF_25") (pintype "passive"))
    )
    (net (code "105") (name "Net-(U4-EN)") (class "Default")
      (node (ref "C45") (pin "2") (pinfunction "2_2") (pintype "passive"))
      (node (ref "R25") (pin "2") (pinfunction "2_2") (pintype "passive"))
      (node (ref "R26") (pin "1") (pinfunction "1_1") (pintype "passive"))
      (node (ref "U4") (pin "3") (pinfunction "EN_3") (pintype "passive"))
    )
    (net (code "106") (name "Net-(U4-FB)") (class "Default")
      (node (ref "R21") (pin "2") (pinfunction "2_2") (pintype "passive"))
      (node (ref "R23") (pin "1") (pinfunction "1_1") (pintype "passive"))
      (node (ref "U4") (pin "5") (pinfunction "FB_5") (pintype "passive"))
    )
    (net (code "107") (name "Net-(U4-LX_1)") (class "Default")
      (node (ref "L4") (pin "2") (pinfunction "2_2") (pintype "passive"))
      (node (ref "U4") (pin "1") (pinfunction "LX_1_1") (pintype "passive"))
      (node (ref "U4") (pin "2") (pinfunction "LX_2_2") (pintype "passive"))
    )
    (net (code "108") (name "Net-(U6-OUTN)") (class "Default")
      (node (ref "FB2") (pin "1") (pinfunction "1_1") (pintype "passive"))
      (node (ref "U6") (pin "10") (pinfunction "OUTN_10") (pintype "passive"))
    )
    (net (code "109") (name "Net-(U6-OUTP)") (class "Default")
      (node (ref "FB1") (pin "1") (pinfunction "1_1") (pintype "passive"))
      (node (ref "U6") (pin "9") (pinfunction "OUTP_9") (pintype "passive"))
    )
    (net (code "110") (name "Net-(U8-OSCO)") (class "Default")
      (node (ref "C56") (pin "1") (pinfunction "1_1") (pintype "passive"))
      (node (ref "U8") (pin "2") (pinfunction "OSCO_2") (pintype "output"))
      (node (ref "X1") (pin "2") (pinfunction "2_2") (pintype "passive"))
    )
    (net (code "111") (name "Net-(U8-~{INT})") (class "Default")
      (node (ref "C54") (pin "2") (pinfunction "2_2") (pintype "passive"))
      (node (ref "R53") (pin "1") (pinfunction "1_1") (pintype "passive"))
      (node (ref "U8") (pin "3") (pinfunction "~{INT}_3") (pintype "input"))
    )
    (net (code "112") (name "Net-(USB_C1-CC1)") (class "Default")
      (node (ref "R4") (pin "1") (pinfunction "1_1") (pintype "passive"))
      (node (ref "USB_C1") (pin "A5") (pinfunction "CC1_A5") (pintype "passive"))
    )
    (net (code "113") (name "Net-(USB_C1-CC2)") (class "Default")
      (node (ref "R5") (pin "1") (pinfunction "1_1") (pintype "passive"))
      (node (ref "USB_C1") (pin "B5") (pinfunction "CC2_B5") (pintype "passive"))
    )
    (net (code "114") (name "Net-(USB_C1-VCC)") (class "Default")
      (node (ref "F1") (pin "2") (pinfunction "2_2") (pintype "passive"))
      (node (ref "USB_C1") (pin "A4") (pinfunction "VCC_A4") (pintype "passive"))
    )
    (net (code "115") (name "PERI_VDD") (class "Default")
      (node (ref "C33") (pin "2") (pinfunction "2_2") (pintype "passive"))
      (node (ref "C43") (pin "1") (pinfunction "1_1") (pintype "passive"))
      (node (ref "C52") (pin "2") (pinfunction "2_2") (pintype "passive"))
      (node (ref "CD1") (pin "4") (pinfunction "VDD_4") (pintype "passive"))
      (node (ref "J2") (pin "8") (pinfunction "8_8") (pintype "passive"))
      (node (ref "R15") (pin "2") (pinfunction "2_2") (pintype "passive"))
      (node (ref "R16") (pin "2") (pinfunction "2_2") (pintype "passive"))
      (node (ref "R17") (pin "2") (pinfunction "2_2") (pintype "passive"))
      (node (ref "R19") (pin "2") (pinfunction "2_2") (pintype "passive"))
      (node (ref "R40") (pin "1") (pinfunction "1_1") (pintype "passive"))
      (node (ref "TP3") (pin "1") (pinfunction "TP_1") (pintype "passive"))
      (node (ref "U3") (pin "12") (pinfunction "LDO2_12") (pintype "passive"))
    )
    (net (code "116") (name "RTC_VDD") (class "Default")
      (node (ref "C29") (pin "2") (pinfunction "2_2") (pintype "passive"))
      (node (ref "C53") (pin "2") (pinfunction "2_2") (pintype "passive"))
      (node (ref "TP5") (pin "1") (pinfunction "TP_1") (pintype "passive"))
      (node (ref "U3") (pin "28") (pinfunction "LDO1_28") (pintype "passive"))
      (node (ref "U3") (pin "29") (pinfunction "SYSEN_29") (pintype "passive"))
      (node (ref "U8") (pin "8") (pinfunction "VDD_8") (pintype "power_in"))
    )
    (net (code "117") (name "SYS_VBAT") (class "Default")
      (node (ref "C20") (pin "1") (pinfunction "1_1") (pintype "passive"))
      (node (ref "C21") (pin "1") (pinfunction "1_1") (pintype "passive"))
      (node (ref "J1") (pin "30") (pinfunction "30_30") (pintype "passive"))
      (node (ref "J5") (pin "1") (pinfunction "1_1") (pintype "passive"))
      (node (ref "TP6") (pin "1") (pinfunction "TP_1") (pintype "passive"))
      (node (ref "U3") (pin "34") (pinfunction "BAT_1_34") (pintype "passive"))
      (node (ref "U3") (pin "35") (pinfunction "BAT_2_35") (pintype "passive"))
    )
    (net (code "118") (name "USB_5V") (class "Default")
      (node (ref "C18") (pin "1") (pinfunction "1_1") (pintype "passive"))
      (node (ref "C19") (pin "1") (pinfunction "1_1") (pintype "passive"))
      (node (ref "C22") (pin "1") (pinfunction "1_1") (pintype "passive"))
      (node (ref "F1") (pin "1") (pinfunction "1_1") (pintype "passive"))
      (node (ref "U2") (pin "7") (pinfunction "REGIN_7") (pintype "power_in"))
      (node (ref "U2") (pin "8") (pinfunction "VBUS_8") (pintype "input"))
      (node (ref "U3") (pin "32") (pinfunction "ACIN_1_32") (pintype "passive"))
      (node (ref "U3") (pin "33") (pinfunction "ACIN_2_33") (pintype "passive"))
    )
    (net (code "119") (name "unconnected-(CD1-DAT1-Pad8)") (class "Default")
      (node (ref "CD1") (pin "8") (pinfunction "DAT1_8") (pintype "passive+no_connect"))
    )
    (net (code "120") (name "unconnected-(CD1-DAT2-Pad1)") (class "Default")
      (node (ref "CD1") (pin "1") (pinfunction "DAT2_1") (pintype "passive+no_connect"))
    )
    (net (code "121") (name "unconnected-(CD1-DETECT-Pad9)") (class "Default")
      (node (ref "CD1") (pin "9") (pinfunction "DETECT_9") (pintype "passive+no_connect"))
    )
    (net (code "122") (name "unconnected-(CD1-SWITCH-Pad10)") (class "Default")
      (node (ref "CD1") (pin "10") (pinfunction "SWITCH_10") (pintype "passive+no_connect"))
    )
    (net (code "123") (name "unconnected-(D8-I{slash}O_3-Pad4)") (class "Default")
      (node (ref "D8") (pin "4") (pinfunction "I/O_3_4") (pintype "bidirectional+no_connect"))
    )
    (net (code "124") (name "unconnected-(J1-Pad25)") (class "Default")
      (node (ref "J1") (pin "25") (pinfunction "25_25") (pintype "passive+no_connect"))
    )
    (net (code "125") (name "unconnected-(J1-Pad27)") (class "Default")
      (node (ref "J1") (pin "27") (pinfunction "27_27") (pintype "passive+no_connect"))
    )
    (net (code "126") (name "unconnected-(J1-Pad29)") (class "Default")
      (node (ref "J1") (pin "29") (pinfunction "29_29") (pintype "passive+no_connect"))
    )
    (net (code "127") (name "unconnected-(J3-Pad7)") (class "Default")
      (node (ref "J3") (pin "7") (pinfunction "7_7") (pintype "passive+no_connect"))
    )
    (net (code "128") (name "unconnected-(J3-Pad8)") (class "Default")
      (node (ref "J3") (pin "8") (pinfunction "8_8") (pintype "passive+no_connect"))
    )
    (net (code "129") (name "unconnected-(J5-MNT_1-Pad3)") (class "Default")
      (node (ref "J5") (pin "3") (pinfunction "MNT_1_3") (pintype "passive+no_connect"))
    )
    (net (code "130") (name "unconnected-(J5-MNT_2-Pad4)") (class "Default")
      (node (ref "J5") (pin "4") (pinfunction "MNT_2_4") (pintype "passive+no_connect"))
    )
    (net (code "131") (name "unconnected-(SW1-Pad1)") (class "Default")
      (node (ref "SW1") (pin "1") (pinfunction "1_1") (pintype "passive"))
    )
    (net (code "132") (name "unconnected-(SW1-Pad4)") (class "Default")
      (node (ref "SW1") (pin "4") (pinfunction "4_4") (pintype "passive"))
    )
    (net (code "133") (name "unconnected-(SW2-Pad3)") (class "Default")
      (node (ref "SW2") (pin "3") (pinfunction "3_3") (pintype "passive"))
    )
    (net (code "134") (name "unconnected-(SW2-Pad4)") (class "Default")
      (node (ref "SW2") (pin "4") (pinfunction "4_4") (pintype "passive"))
    )
    (net (code "135") (name "unconnected-(U1-SENSOR_CAPP-Pad6)") (class "Default")
      (node (ref "U1") (pin "6") (pinfunction "SENSOR_CAPP_6") (pintype "input+no_connect"))
    )
    (net (code "136") (name "unconnected-(U2-CTS-Pad18)") (class "Default")
      (node (ref "U2") (pin "18") (pinfunction "CTS_18") (pintype "input+no_connect"))
    )
    (net (code "137") (name "unconnected-(U2-DCD-Pad24)") (class "Default")
      (node (ref "U2") (pin "24") (pinfunction "DCD_24") (pintype "input+no_connect"))
    )
    (net (code "138") (name "unconnected-(U2-DSR-Pad22)") (class "Default")
      (node (ref "U2") (pin "22") (pinfunction "DSR_22") (pintype "input+no_connect"))
    )
    (net (code "139") (name "unconnected-(U2-GPIO.0-Pad14)") (class "Default")
      (node (ref "U2") (pin "14") (pinfunction "GPIO.0_14") (pintype "bidirectional+no_connect"))
    )
    (net (code "140") (name "unconnected-(U2-GPIO.1-Pad13)") (class "Default")
      (node (ref "U2") (pin "13") (pinfunction "GPIO.1_13") (pintype "bidirectional+no_connect"))
    )
    (net (code "141") (name "unconnected-(U2-GPIO.2-Pad12)") (class "Default")
      (node (ref "U2") (pin "12") (pinfunction "GPIO.2_12") (pintype "bidirectional+no_connect"))
    )
    (net (code "142") (name "unconnected-(U2-GPIO.3-Pad11)") (class "Default")
      (node (ref "U2") (pin "11") (pinfunction "GPIO.3_11") (pintype "bidirectional+no_connect"))
    )
    (net (code "143") (name "unconnected-(U2-NC-Pad10)") (class "Default")
      (node (ref "U2") (pin "10") (pinfunction "NC_10") (pintype "passive+no_connect"))
    )
    (net (code "144") (name "unconnected-(U2-RI-Pad1)") (class "Default")
      (node (ref "U2") (pin "1") (pinfunction "RI_1") (pintype "input+no_connect"))
    )
    (net (code "145") (name "unconnected-(U2-SUSPEND-Pad17)") (class "Default")
      (node (ref "U2") (pin "17") (pinfunction "SUSPEND_17") (pintype "output+no_connect"))
    )
    (net (code "146") (name "unconnected-(U2-VPP-Pad16)") (class "Default")
      (node (ref "U2") (pin "16") (pinfunction "VPP_16") (pintype "power_in+no_connect"))
    )
    (net (code "147") (name "unconnected-(U2-~{SUSPEND}-Pad15)") (class "Default")
      (node (ref "U2") (pin "15") (pinfunction "~{SUSPEND}_15") (pintype "output+no_connect"))
    )
    (net (code "148") (name "unconnected-(U3-CHGLED-Pad36)") (class "Default")
      (node (ref "U3") (pin "36") (pinfunction "CHGLED_36") (pintype "passive+no_connect"))
    )
    (net (code "149") (name "unconnected-(U3-DCDC2-Pad10)") (class "Default")
      (node (ref "U3") (pin "10") (pinfunction "DCDC2_10") (pintype "passive+no_connect"))
    )
    (net (code "150") (name "unconnected-(U3-GPIO3-Pad41)") (class "Default")
      (node (ref "U3") (pin "41") (pinfunction "GPIO3_41") (pintype "passive+no_connect"))
    )
    (net (code "151") (name "unconnected-(U3-IRQ-Pad48)") (class "Default")
      (node (ref "U3") (pin "48") (pinfunction "IRQ_48") (pintype "passive+no_connect"))
    )
    (net (code "152") (name "unconnected-(U3-LX2-Pad8)") (class "Default")
      (node (ref "U3") (pin "8") (pinfunction "LX2_8") (pintype "passive+no_connect"))
    )
    (net (code "153") (name "unconnected-(U3-NC-Pad43)") (class "Default")
      (node (ref "U3") (pin "43") (pinfunction "NC_43") (pintype "passive+no_connect"))
    )
    (net (code "154") (name "unconnected-(U3-N_RSTO-Pad3)") (class "Default")
      (node (ref "U3") (pin "3") (pinfunction "N_RSTO_3") (pintype "passive+no_connect"))
    )
    (net (code "155") (name "unconnected-(U3-PWREN-Pad27)") (class "Default")
      (node (ref "U3") (pin "27") (pinfunction "PWREN_27") (pintype "passive+no_connect"))
    )
    (net (code "156") (name "unconnected-(U6-NC-Pad5)") (class "Default")
      (node (ref "U6") (pin "5") (pinfunction "NC_5") (pintype "passive+no_connect"))
    )
    (net (code "157") (name "unconnected-(U6-NC-Pad6)") (class "Default")
      (node (ref "U6") (pin "6") (pinfunction "NC_6") (pintype "passive+no_connect"))
    )
    (net (code "158") (name "unconnected-(U6-NC-Pad12)") (class "Default")
      (node (ref "U6") (pin "12") (pinfunction "NC_12") (pintype "passive+no_connect"))
    )
    (net (code "159") (name "unconnected-(U6-NC-Pad13)") (class "Default")
      (node (ref "U6") (pin "13") (pinfunction "NC_13") (pintype "passive+no_connect"))
    )
    (net (code "160") (name "unconnected-(U8-CLKOUT-Pad7)") (class "Default")
      (node (ref "U8") (pin "7") (pinfunction "CLKOUT_7") (pintype "output+no_connect"))
    )
  )
)
